# reg-board.net
KiCad netlist of a schematic drawn in EAGLE
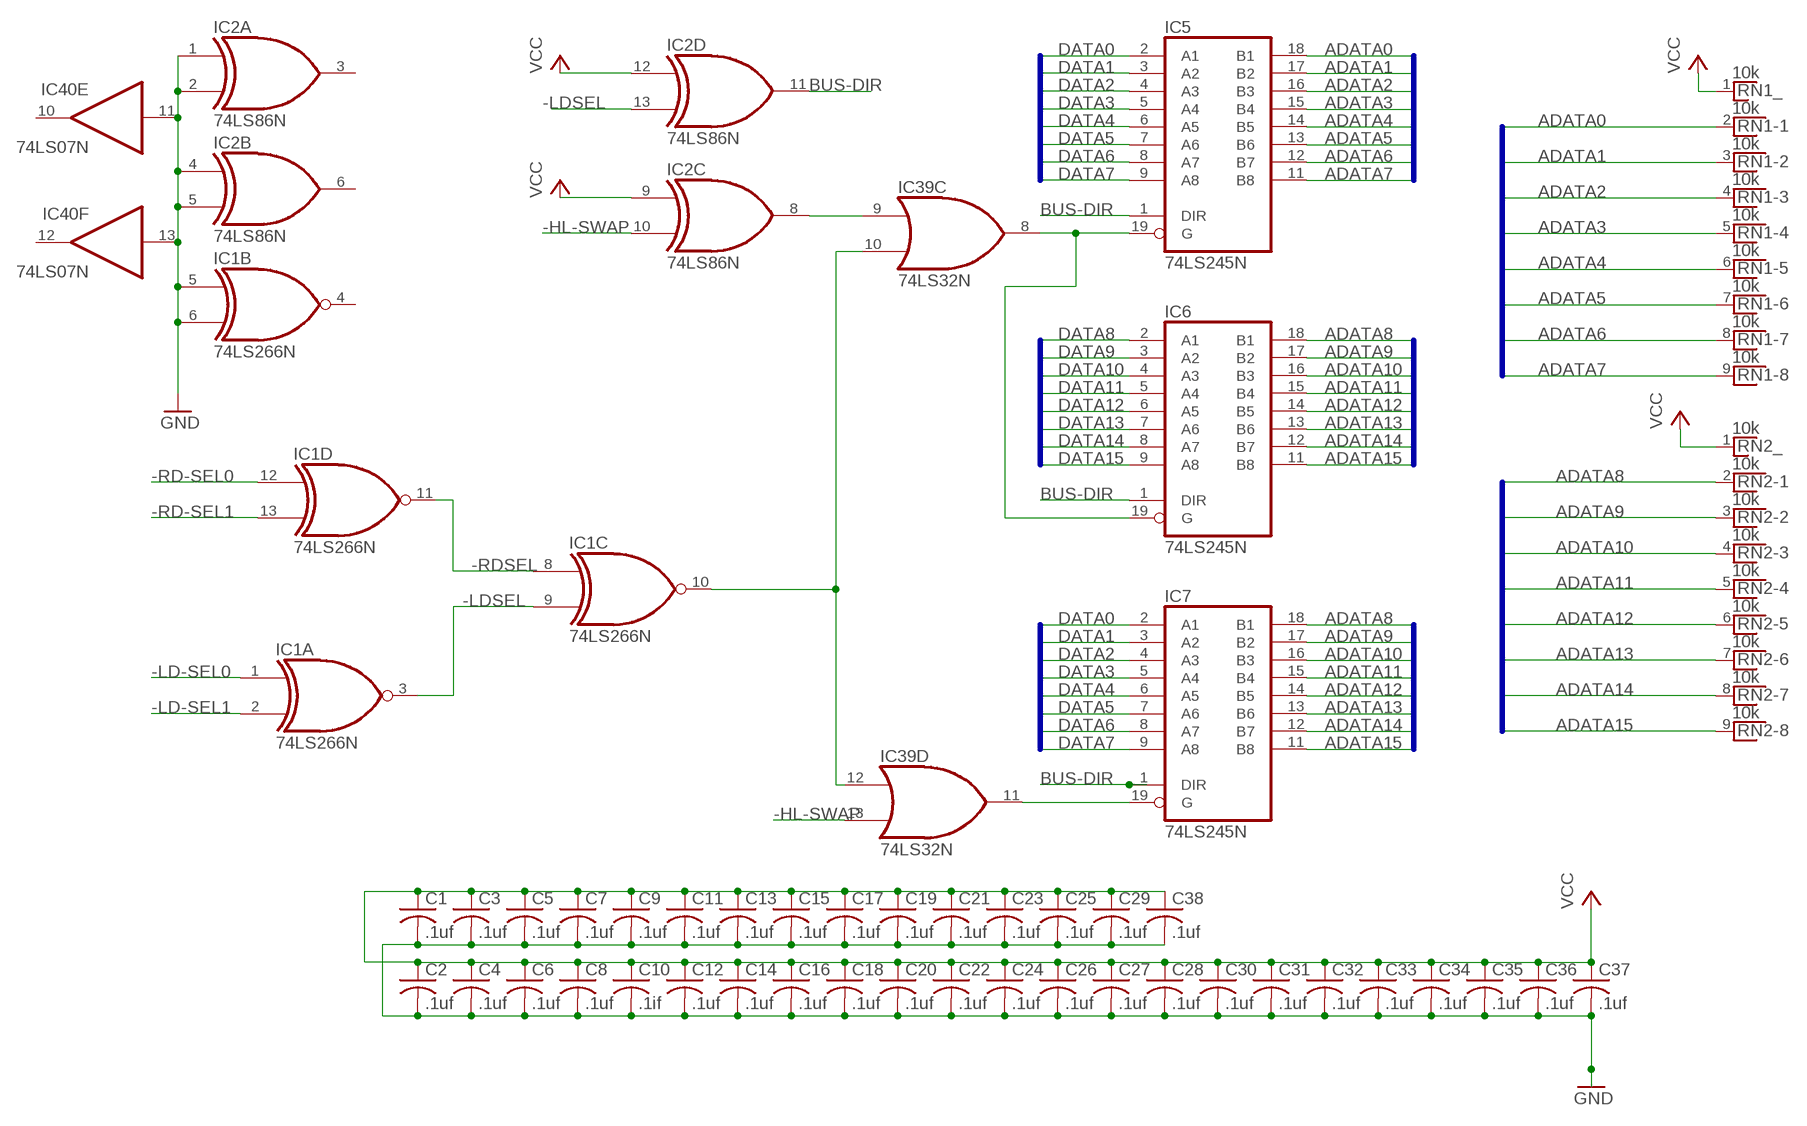
[diagram p0: schematic, sheet 1]
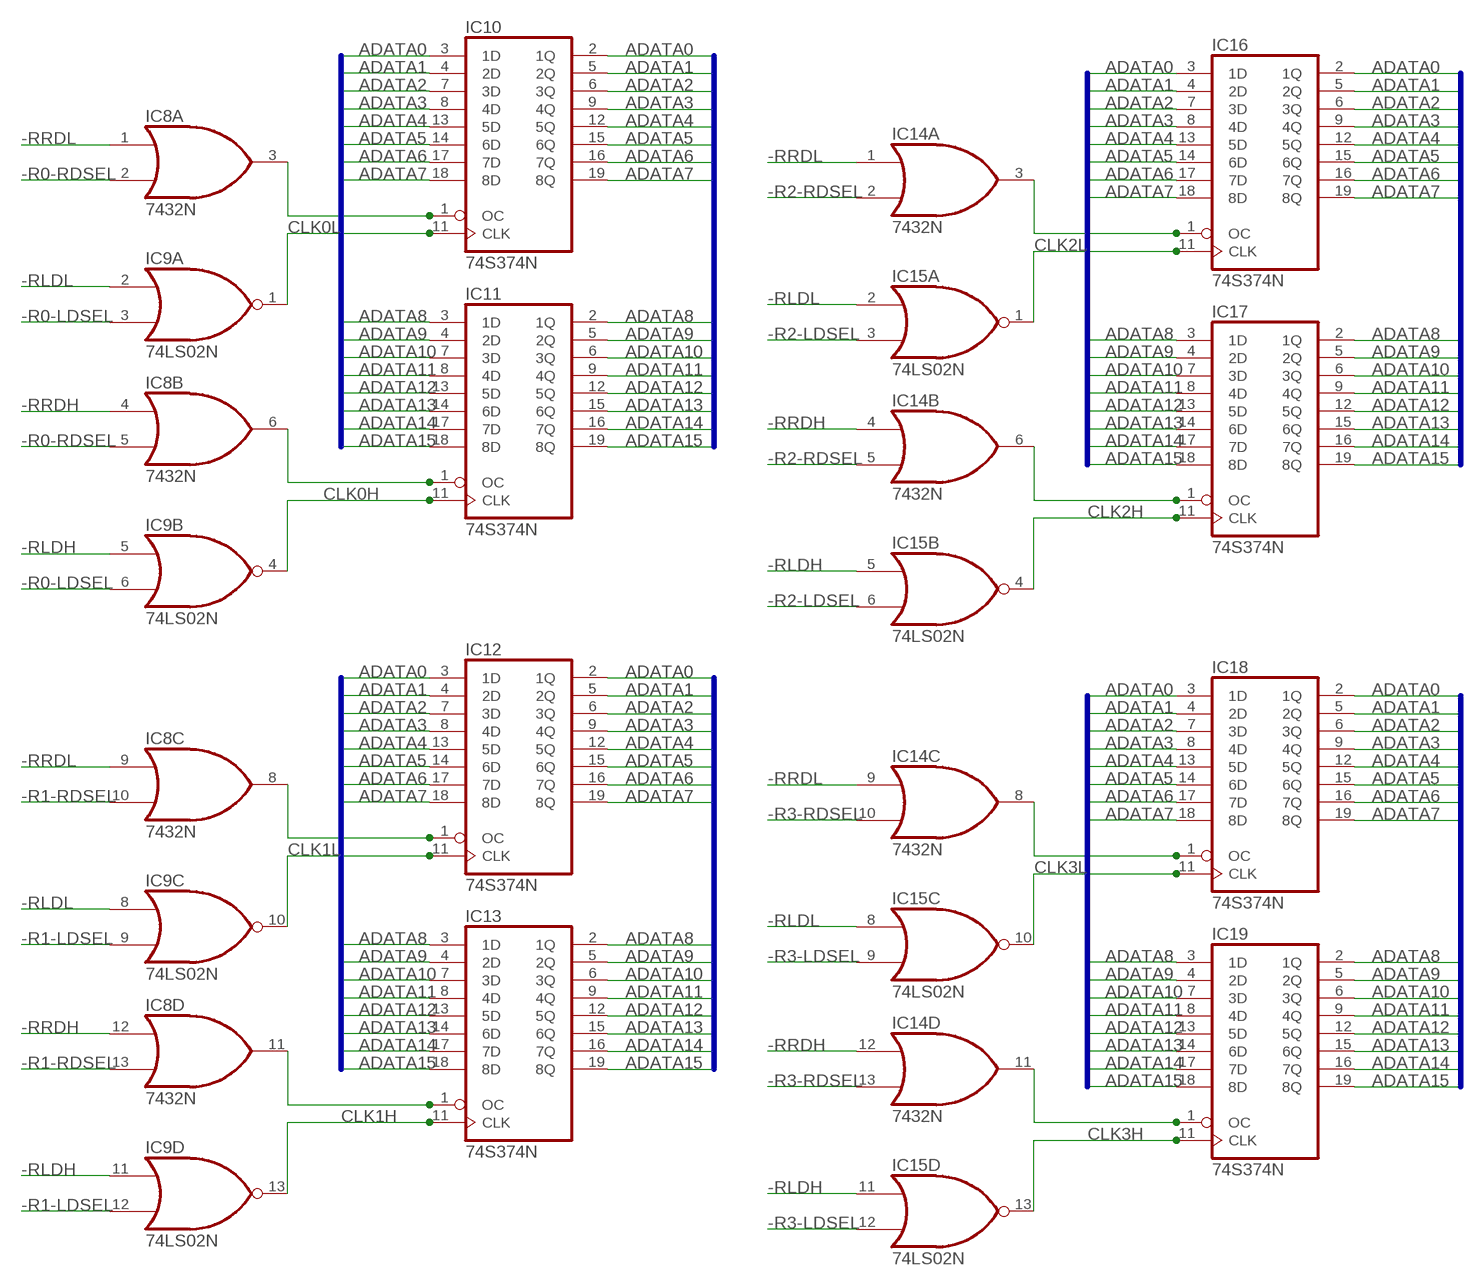
[diagram p1: schematic, sheet 2]
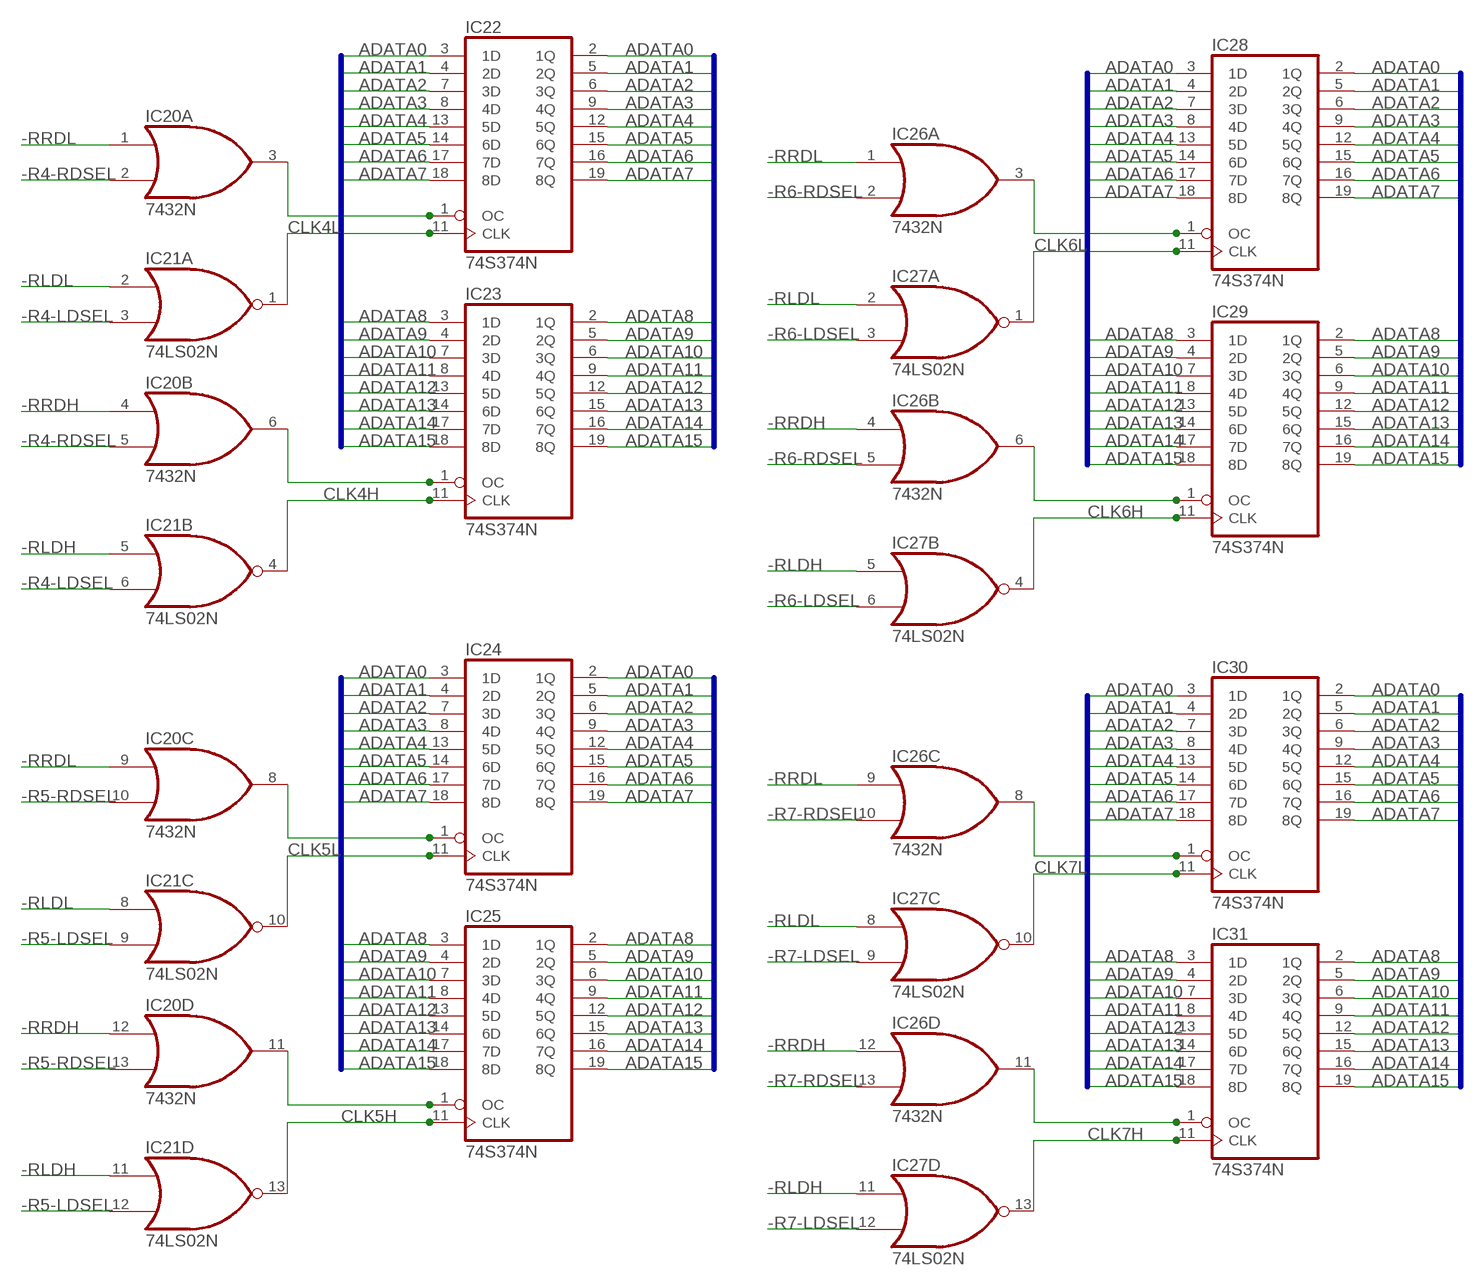
[diagram p2: schematic, sheet 3]
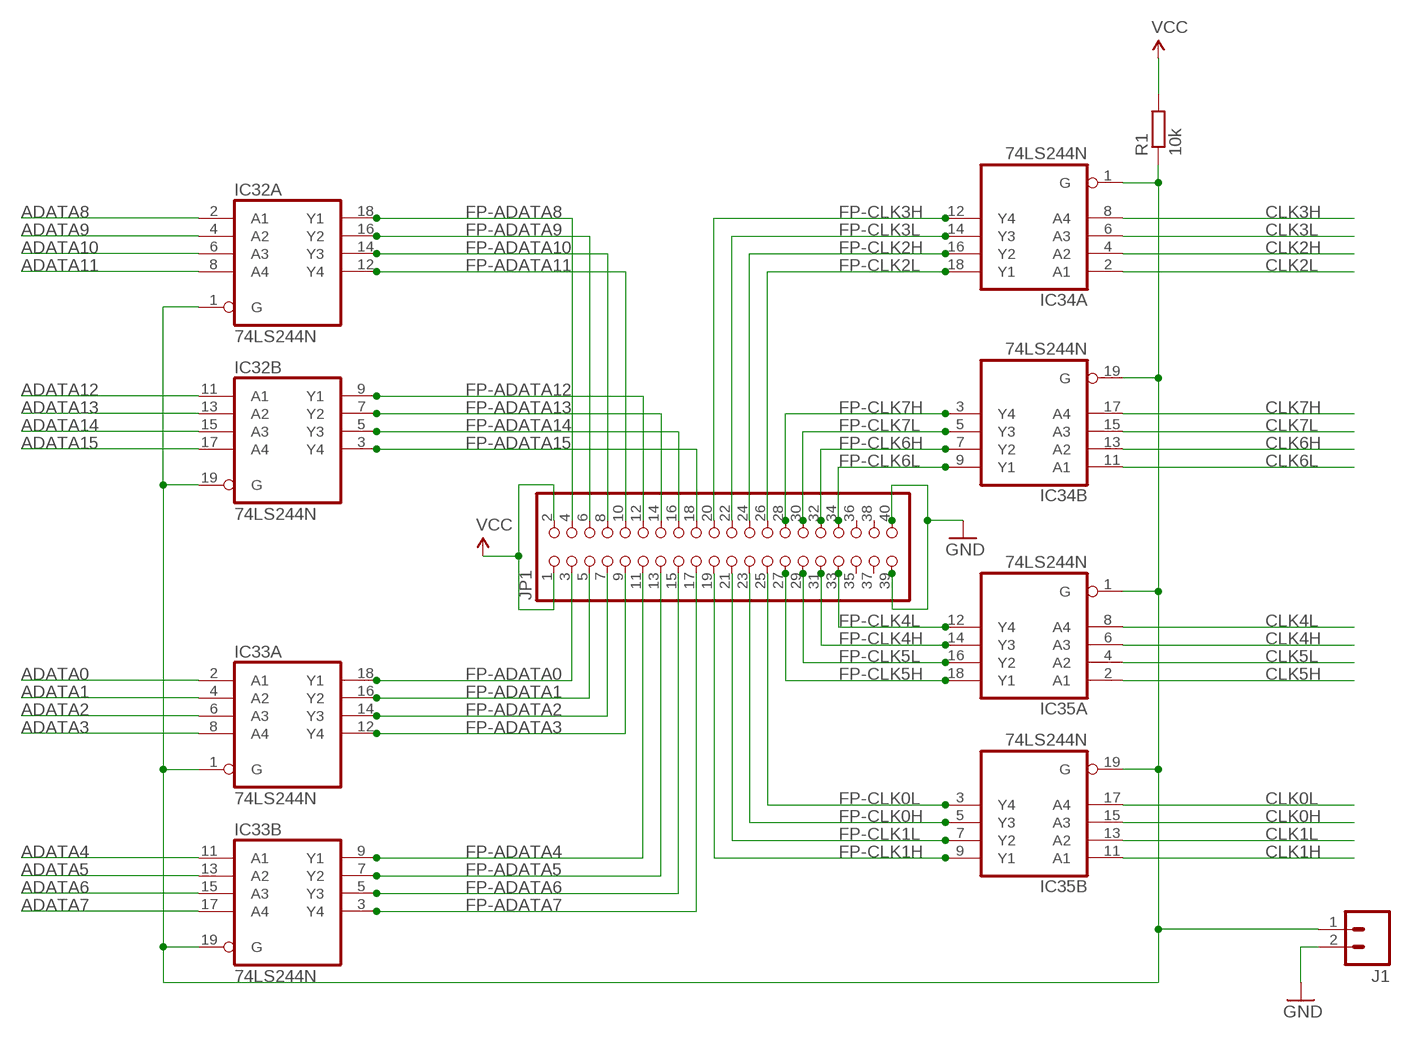
[diagram p3: schematic, sheet 4]
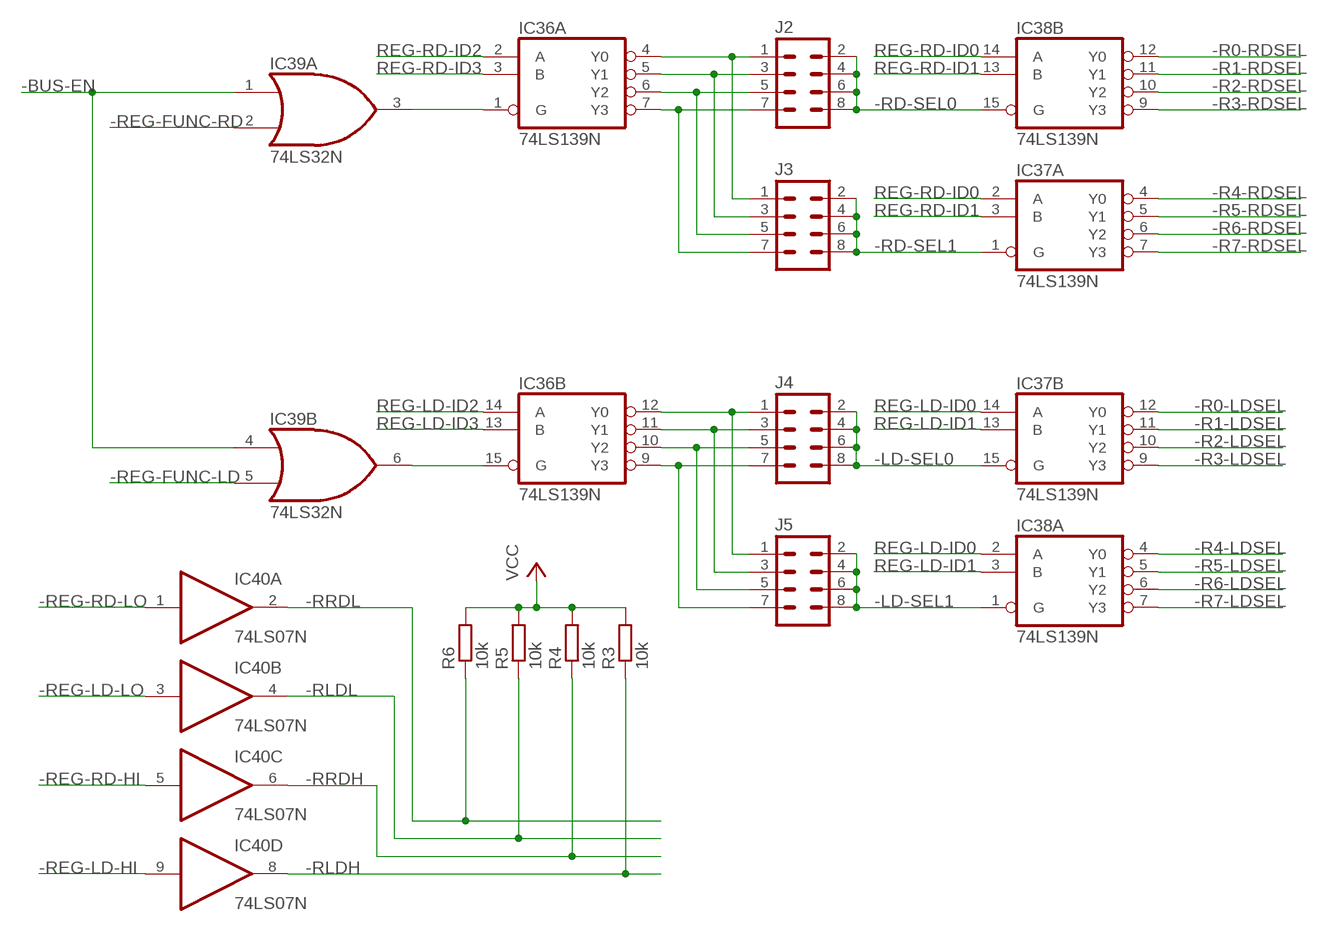
[diagram p4: schematic, sheet 5]
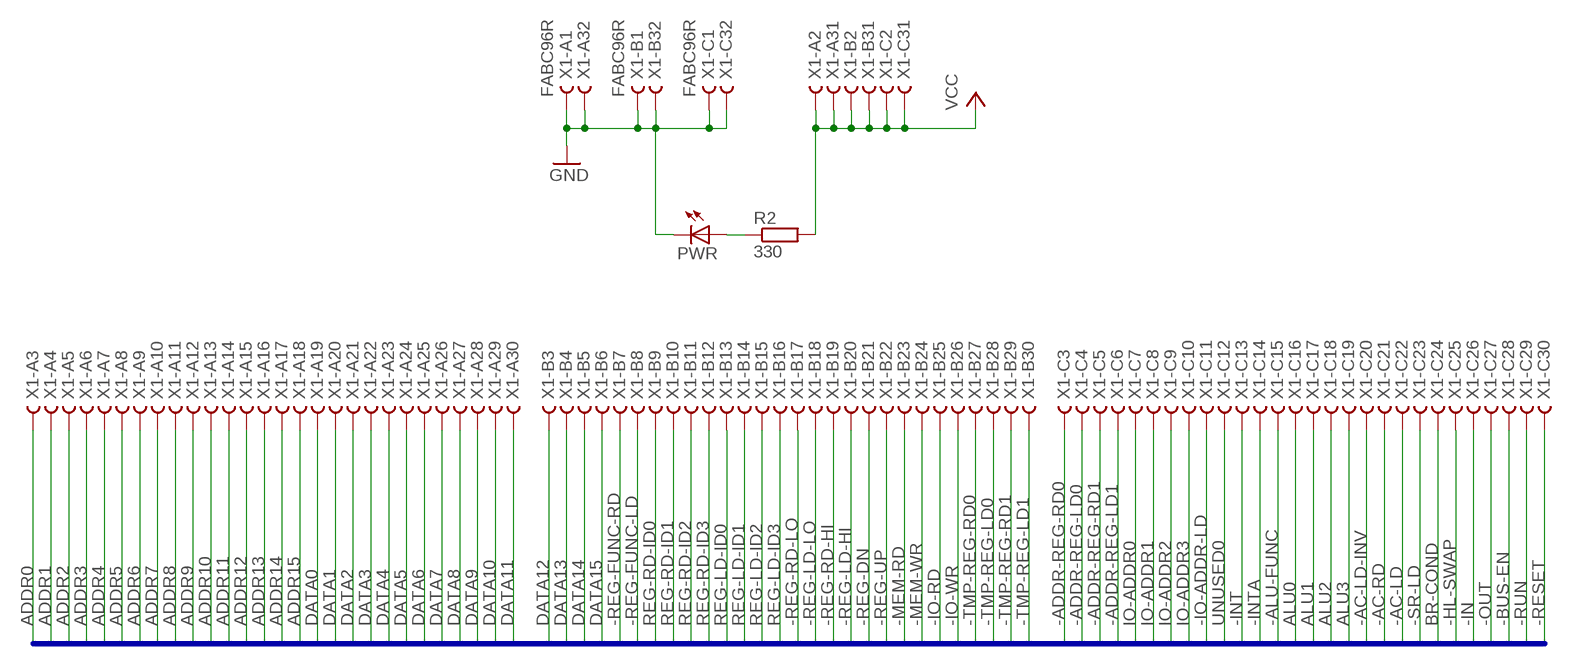
[diagram p5: schematic, sheet 6]

(export (version "E")
  (design (tool "Eeschema 10.0.6"))
  (components
    (comp (ref "IC8")
      (value "7432N")
      (footprint "eagle-import:DIL14")
      (libsource (lib "eagle-import") (part "7432N"))
    )
    (comp (ref "IC9")
      (value "74LS02N")
      (footprint "eagle-import:DIL14")
      (libsource (lib "eagle-import") (part "7402NLS"))
    )
    (comp (ref "IC10")
      (value "74S374N")
      (footprint "eagle-import:DIL20")
      (libsource (lib "eagle-import") (part "74374NS"))
    )
    (comp (ref "IC11")
      (value "74S374N")
      (footprint "eagle-import:DIL20")
      (libsource (lib "eagle-import") (part "74374NS"))
    )
    (comp (ref "IC12")
      (value "74S374N")
      (footprint "eagle-import:DIL20")
      (libsource (lib "eagle-import") (part "74374NS"))
    )
    (comp (ref "IC13")
      (value "74S374N")
      (footprint "eagle-import:DIL20")
      (libsource (lib "eagle-import") (part "74374NS"))
    )
    (comp (ref "IC14")
      (value "7432N")
      (footprint "eagle-import:DIL14")
      (libsource (lib "eagle-import") (part "7432N"))
    )
    (comp (ref "IC15")
      (value "74LS02N")
      (footprint "eagle-import:DIL14")
      (libsource (lib "eagle-import") (part "7402NLS"))
    )
    (comp (ref "IC16")
      (value "74S374N")
      (footprint "eagle-import:DIL20")
      (libsource (lib "eagle-import") (part "74374NS"))
    )
    (comp (ref "IC17")
      (value "74S374N")
      (footprint "eagle-import:DIL20")
      (libsource (lib "eagle-import") (part "74374NS"))
    )
    (comp (ref "IC18")
      (value "74S374N")
      (footprint "eagle-import:DIL20")
      (libsource (lib "eagle-import") (part "74374NS"))
    )
    (comp (ref "IC19")
      (value "74S374N")
      (footprint "eagle-import:DIL20")
      (libsource (lib "eagle-import") (part "74374NS"))
    )
    (comp (ref "C1")
      (value ".1uf")
      (footprint "eagle-import:C025-040X050")
      (libsource (lib "eagle-import") (part "C-US025-040X050"))
    )
    (comp (ref "C2")
      (value ".1uf")
      (footprint "eagle-import:C025-040X050")
      (libsource (lib "eagle-import") (part "C-US025-040X050"))
    )
    (comp (ref "C3")
      (value ".1uf")
      (footprint "eagle-import:C025-040X050")
      (libsource (lib "eagle-import") (part "C-US025-040X050"))
    )
    (comp (ref "C4")
      (value ".1uf")
      (footprint "eagle-import:C025-040X050")
      (libsource (lib "eagle-import") (part "C-US025-040X050"))
    )
    (comp (ref "C5")
      (value ".1uf")
      (footprint "eagle-import:C025-040X050")
      (libsource (lib "eagle-import") (part "C-US025-040X050"))
    )
    (comp (ref "C6")
      (value ".1uf")
      (footprint "eagle-import:C025-040X050")
      (libsource (lib "eagle-import") (part "C-US025-040X050"))
    )
    (comp (ref "C7")
      (value ".1uf")
      (footprint "eagle-import:C025-040X050")
      (libsource (lib "eagle-import") (part "C-US025-040X050"))
    )
    (comp (ref "C8")
      (value ".1uf")
      (footprint "eagle-import:C025-040X050")
      (libsource (lib "eagle-import") (part "C-US025-040X050"))
    )
    (comp (ref "C9")
      (value ".1uf")
      (footprint "eagle-import:C025-040X050")
      (libsource (lib "eagle-import") (part "C-US025-040X050"))
    )
    (comp (ref "C10")
      (value ".1if")
      (footprint "eagle-import:C025-040X050")
      (libsource (lib "eagle-import") (part "C-US025-040X050"))
    )
    (comp (ref "C11")
      (value ".1uf")
      (footprint "eagle-import:C025-040X050")
      (libsource (lib "eagle-import") (part "C-US025-040X050"))
    )
    (comp (ref "C12")
      (value ".1uf")
      (footprint "eagle-import:C025-040X050")
      (libsource (lib "eagle-import") (part "C-US025-040X050"))
    )
    (comp (ref "C13")
      (value ".1uf")
      (footprint "eagle-import:C025-040X050")
      (libsource (lib "eagle-import") (part "C-US025-040X050"))
    )
    (comp (ref "C14")
      (value ".1uf")
      (footprint "eagle-import:C025-040X050")
      (libsource (lib "eagle-import") (part "C-US025-040X050"))
    )
    (comp (ref "C15")
      (value ".1uf")
      (footprint "eagle-import:C025-040X050")
      (libsource (lib "eagle-import") (part "C-US025-040X050"))
    )
    (comp (ref "C16")
      (value ".1uf")
      (footprint "eagle-import:C025-040X050")
      (libsource (lib "eagle-import") (part "C-US025-040X050"))
    )
    (comp (ref "C17")
      (value ".1uf")
      (footprint "eagle-import:C025-040X050")
      (libsource (lib "eagle-import") (part "C-US025-040X050"))
    )
    (comp (ref "C18")
      (value ".1uf")
      (footprint "eagle-import:C025-040X050")
      (libsource (lib "eagle-import") (part "C-US025-040X050"))
    )
    (comp (ref "C19")
      (value ".1uf")
      (footprint "eagle-import:C025-040X050")
      (libsource (lib "eagle-import") (part "C-US025-040X050"))
    )
    (comp (ref "C20")
      (value ".1uf")
      (footprint "eagle-import:C025-040X050")
      (libsource (lib "eagle-import") (part "C-US025-040X050"))
    )
    (comp (ref "C21")
      (value ".1uf")
      (footprint "eagle-import:C025-040X050")
      (libsource (lib "eagle-import") (part "C-US025-040X050"))
    )
    (comp (ref "C22")
      (value ".1uf")
      (footprint "eagle-import:C025-040X050")
      (libsource (lib "eagle-import") (part "C-US025-040X050"))
    )
    (comp (ref "C23")
      (value ".1uf")
      (footprint "eagle-import:C025-040X050")
      (libsource (lib "eagle-import") (part "C-US025-040X050"))
    )
    (comp (ref "C24")
      (value ".1uf")
      (footprint "eagle-import:C025-040X050")
      (libsource (lib "eagle-import") (part "C-US025-040X050"))
    )
    (comp (ref "C25")
      (value ".1uf")
      (footprint "eagle-import:C025-040X050")
      (libsource (lib "eagle-import") (part "C-US025-040X050"))
    )
    (comp (ref "C26")
      (value ".1uf")
      (footprint "eagle-import:C025-040X050")
      (libsource (lib "eagle-import") (part "C-US025-040X050"))
    )
    (comp (ref "C27")
      (value ".1uf")
      (footprint "eagle-import:C025-040X050")
      (libsource (lib "eagle-import") (part "C-US025-040X050"))
    )
    (comp (ref "C28")
      (value ".1uf")
      (footprint "eagle-import:C025-040X050")
      (libsource (lib "eagle-import") (part "C-US025-040X050"))
    )
    (comp (ref "C29")
      (value ".1uf")
      (footprint "eagle-import:C025-040X050")
      (libsource (lib "eagle-import") (part "C-US025-040X050"))
    )
    (comp (ref "C30")
      (value ".1uf")
      (footprint "eagle-import:C025-040X050")
      (libsource (lib "eagle-import") (part "C-US025-040X050"))
    )
    (comp (ref "C31")
      (value ".1uf")
      (footprint "eagle-import:C025-040X050")
      (libsource (lib "eagle-import") (part "C-US025-040X050"))
    )
    (comp (ref "C32")
      (value ".1uf")
      (footprint "eagle-import:C025-040X050")
      (libsource (lib "eagle-import") (part "C-US025-040X050"))
    )
    (comp (ref "C33")
      (value ".1uf")
      (footprint "eagle-import:C025-040X050")
      (libsource (lib "eagle-import") (part "C-US025-040X050"))
    )
    (comp (ref "C34")
      (value ".1uf")
      (footprint "eagle-import:C025-040X050")
      (libsource (lib "eagle-import") (part "C-US025-040X050"))
    )
    (comp (ref "C35")
      (value ".1uf")
      (footprint "eagle-import:C025-040X050")
      (libsource (lib "eagle-import") (part "C-US025-040X050"))
    )
    (comp (ref "C36")
      (value ".1uf")
      (footprint "eagle-import:C025-040X050")
      (libsource (lib "eagle-import") (part "C-US025-040X050"))
    )
    (comp (ref "C37")
      (value ".1uf")
      (footprint "eagle-import:C025-040X050")
      (libsource (lib "eagle-import") (part "C-US025-040X050"))
    )
    (comp (ref "C38")
      (value ".1uf")
      (footprint "eagle-import:C025-040X050")
      (libsource (lib "eagle-import") (part "C-US025-040X050"))
    )
    (comp (ref "IC1")
      (value "74LS266N")
      (footprint "eagle-import:DIL14")
      (libsource (lib "eagle-import") (part "74266NLS"))
    )
    (comp (ref "IC2")
      (value "74LS86N")
      (footprint "eagle-import:DIL14")
      (libsource (lib "eagle-import") (part "7486NLS"))
    )
    (comp (ref "IC5")
      (value "74LS245N")
      (footprint "eagle-import:DIL20")
      (libsource (lib "eagle-import") (part "74245NLS"))
    )
    (comp (ref "IC6")
      (value "74LS245N")
      (footprint "eagle-import:DIL20")
      (libsource (lib "eagle-import") (part "74245NLS"))
    )
    (comp (ref "IC7")
      (value "74LS245N")
      (footprint "eagle-import:DIL20")
      (libsource (lib "eagle-import") (part "74245NLS"))
    )
    (comp (ref "IC39")
      (value "74LS32N")
      (footprint "eagle-import:DIL14")
      (libsource (lib "eagle-import") (part "74xx-us_88_7432NLS"))
    )
    (comp (ref "IC40")
      (value "74LS07N")
      (footprint "eagle-import:DIL14")
      (libsource (lib "eagle-import") (part "7407NLS"))
    )
    (comp (ref "RN1")
      (value "10k")
      (footprint "eagle-import:RN-9")
      (libsource (lib "eagle-import") (part "RNX8"))
    )
    (comp (ref "RN2")
      (value "10k")
      (footprint "eagle-import:RN-9")
      (libsource (lib "eagle-import") (part "RNX8"))
    )
    (comp (ref "IC36")
      (value "74LS139N")
      (footprint "eagle-import:DIL16")
      (libsource (lib "eagle-import") (part "74139NLS"))
    )
    (comp (ref "IC37")
      (value "74LS139N")
      (footprint "eagle-import:DIL16")
      (libsource (lib "eagle-import") (part "74139NLS"))
    )
    (comp (ref "IC38")
      (value "74LS139N")
      (footprint "eagle-import:DIL16")
      (libsource (lib "eagle-import") (part "74139NLS"))
    )
    (comp (ref "J2")
      (value "M04X2")
      (footprint "eagle-import:2X4")
      (libsource (lib "eagle-import") (part "M04X2"))
    )
    (comp (ref "J3")
      (value "M04X2")
      (footprint "eagle-import:2X4")
      (libsource (lib "eagle-import") (part "M04X2"))
    )
    (comp (ref "J4")
      (value "M04X2")
      (footprint "eagle-import:2X4")
      (libsource (lib "eagle-import") (part "M04X2"))
    )
    (comp (ref "J5")
      (value "M04X2")
      (footprint "eagle-import:2X4")
      (libsource (lib "eagle-import") (part "M04X2"))
    )
    (comp (ref "R3")
      (value "10k")
      (footprint "eagle-import:0207_10")
      (libsource (lib "eagle-import") (part "R0207/10"))
    )
    (comp (ref "R4")
      (value "10k")
      (footprint "eagle-import:0207_10")
      (libsource (lib "eagle-import") (part "R0207/10"))
    )
    (comp (ref "R5")
      (value "10k")
      (footprint "eagle-import:0207_10")
      (libsource (lib "eagle-import") (part "R0207/10"))
    )
    (comp (ref "R6")
      (value "10k")
      (footprint "eagle-import:0207_10")
      (libsource (lib "eagle-import") (part "R0207/10"))
    )
    (comp (ref "PWR")
      (value "LED5MM")
      (footprint "eagle-import:LED5MM")
      (libsource (lib "eagle-import") (part "LED5MM"))
    )
    (comp (ref "R2")
      (value "330")
      (footprint "eagle-import:0207_10")
      (libsource (lib "eagle-import") (part "R0207/10"))
    )
    (comp (ref "X1")
      (value "FABC96R")
      (footprint "eagle-import:FABC96R")
      (libsource (lib "eagle-import") (part "FABC96R"))
    )
    (comp (ref "IC20")
      (value "7432N")
      (footprint "eagle-import:DIL14")
      (libsource (lib "eagle-import") (part "7432N"))
    )
    (comp (ref "IC21")
      (value "74LS02N")
      (footprint "eagle-import:DIL14")
      (libsource (lib "eagle-import") (part "7402NLS"))
    )
    (comp (ref "IC22")
      (value "74S374N")
      (footprint "eagle-import:DIL20")
      (libsource (lib "eagle-import") (part "74374NS"))
    )
    (comp (ref "IC23")
      (value "74S374N")
      (footprint "eagle-import:DIL20")
      (libsource (lib "eagle-import") (part "74374NS"))
    )
    (comp (ref "IC24")
      (value "74S374N")
      (footprint "eagle-import:DIL20")
      (libsource (lib "eagle-import") (part "74374NS"))
    )
    (comp (ref "IC25")
      (value "74S374N")
      (footprint "eagle-import:DIL20")
      (libsource (lib "eagle-import") (part "74374NS"))
    )
    (comp (ref "IC26")
      (value "7432N")
      (footprint "eagle-import:DIL14")
      (libsource (lib "eagle-import") (part "7432N"))
    )
    (comp (ref "IC27")
      (value "74LS02N")
      (footprint "eagle-import:DIL14")
      (libsource (lib "eagle-import") (part "7402NLS"))
    )
    (comp (ref "IC28")
      (value "74S374N")
      (footprint "eagle-import:DIL20")
      (libsource (lib "eagle-import") (part "74374NS"))
    )
    (comp (ref "IC29")
      (value "74S374N")
      (footprint "eagle-import:DIL20")
      (libsource (lib "eagle-import") (part "74374NS"))
    )
    (comp (ref "IC30")
      (value "74S374N")
      (footprint "eagle-import:DIL20")
      (libsource (lib "eagle-import") (part "74374NS"))
    )
    (comp (ref "IC31")
      (value "74S374N")
      (footprint "eagle-import:DIL20")
      (libsource (lib "eagle-import") (part "74374NS"))
    )
    (comp (ref "IC32")
      (value "74LS244N")
      (footprint "eagle-import:DIL20")
      (libsource (lib "eagle-import") (part "74xx-us_74244NLS"))
    )
    (comp (ref "IC33")
      (value "74LS244N")
      (footprint "eagle-import:DIL20")
      (libsource (lib "eagle-import") (part "74xx-us_74244NLS"))
    )
    (comp (ref "IC34")
      (value "74LS244N")
      (footprint "eagle-import:DIL20")
      (libsource (lib "eagle-import") (part "74xx-us_74244NLS"))
    )
    (comp (ref "IC35")
      (value "74LS244N")
      (footprint "eagle-import:DIL20")
      (libsource (lib "eagle-import") (part "74xx-us_74244NLS"))
    )
    (comp (ref "J1")
      (value "M02PTH")
      (footprint "eagle-import:1X02")
      (libsource (lib "eagle-import") (part "M02PTH"))
    )
    (comp (ref "JP1")
      (value "PINHD-2X20")
      (footprint "eagle-import:2X20")
      (libsource (lib "eagle-import") (part "PINHD-2X20"))
    )
    (comp (ref "R1")
      (value "10k")
      (footprint "eagle-import:0207_10")
      (libsource (lib "eagle-import") (part "R0207/10"))
    )
  )
  (nets
    (net (code "1") (name "-AC-LD") (class "Default")
      (node (ref "X1") (pin "C22") (pinfunction "B_C22") (pintype "passive"))
    )
    (net (code "2") (name "-AC-LD-INV") (class "Default")
      (node (ref "X1") (pin "C20") (pinfunction "B_C20") (pintype "passive"))
    )
    (net (code "3") (name "-AC-RD") (class "Default")
      (node (ref "X1") (pin "C21") (pinfunction "B_C21") (pintype "passive"))
    )
    (net (code "4") (name "-ADDR-REG-LD0") (class "Default")
      (node (ref "X1") (pin "C4") (pinfunction "B_C4") (pintype "passive"))
    )
    (net (code "5") (name "-ADDR-REG-LD1") (class "Default")
      (node (ref "X1") (pin "C6") (pinfunction "B_C6") (pintype "passive"))
    )
    (net (code "6") (name "-ADDR-REG-RD0") (class "Default")
      (node (ref "X1") (pin "C3") (pinfunction "B_C3") (pintype "passive"))
    )
    (net (code "7") (name "-ADDR-REG-RD1") (class "Default")
      (node (ref "X1") (pin "C5") (pinfunction "B_C5") (pintype "passive"))
    )
    (net (code "8") (name "-ALU-FUNC") (class "Default")
      (node (ref "X1") (pin "C15") (pinfunction "B_C15") (pintype "passive"))
    )
    (net (code "9") (name "-BUS-EN") (class "Default")
      (node (ref "IC39") (pin "1") (pinfunction "I0_1") (pintype "input"))
      (node (ref "IC39") (pin "4") (pinfunction "I0_4") (pintype "input"))
      (node (ref "X1") (pin "C28") (pinfunction "B_C28") (pintype "passive"))
    )
    (net (code "10") (name "-HL-SWAP") (class "Default")
      (node (ref "IC2") (pin "10") (pinfunction "I1_10") (pintype "input"))
      (node (ref "IC39") (pin "13") (pinfunction "I1_13") (pintype "input"))
      (node (ref "X1") (pin "C25") (pinfunction "B_C25") (pintype "passive"))
    )
    (net (code "11") (name "-IN") (class "Default")
      (node (ref "X1") (pin "C26") (pinfunction "B_C26") (pintype "passive"))
    )
    (net (code "12") (name "-INT") (class "Default")
      (node (ref "X1") (pin "C13") (pinfunction "B_C13") (pintype "passive"))
    )
    (net (code "13") (name "-INTA") (class "Default")
      (node (ref "X1") (pin "C14") (pinfunction "B_C14") (pintype "passive"))
    )
    (net (code "14") (name "-IO-ADDR-LD") (class "Default")
      (node (ref "X1") (pin "C11") (pinfunction "B_C11") (pintype "passive"))
    )
    (net (code "15") (name "-IO-RD") (class "Default")
      (node (ref "X1") (pin "B25") (pinfunction "B_B25") (pintype "passive"))
    )
    (net (code "16") (name "-IO-WR") (class "Default")
      (node (ref "X1") (pin "B26") (pinfunction "B_B26") (pintype "passive"))
    )
    (net (code "17") (name "-LD-SEL0") (class "Default")
      (node (ref "IC1") (pin "1") (pinfunction "I0_1") (pintype "input"))
      (node (ref "IC37") (pin "15") (pinfunction "G_15") (pintype "input"))
      (node (ref "J4") (pin "2") (pinfunction "2_2") (pintype "passive"))
      (node (ref "J4") (pin "4") (pinfunction "4_4") (pintype "passive"))
      (node (ref "J4") (pin "6") (pinfunction "6_6") (pintype "passive"))
      (node (ref "J4") (pin "8") (pinfunction "8_8") (pintype "passive"))
    )
    (net (code "18") (name "-LD-SEL1") (class "Default")
      (node (ref "IC1") (pin "2") (pinfunction "I1_2") (pintype "input"))
      (node (ref "IC38") (pin "1") (pinfunction "G_1") (pintype "input"))
      (node (ref "J5") (pin "2") (pinfunction "2_2") (pintype "passive"))
      (node (ref "J5") (pin "4") (pinfunction "4_4") (pintype "passive"))
      (node (ref "J5") (pin "6") (pinfunction "6_6") (pintype "passive"))
      (node (ref "J5") (pin "8") (pinfunction "8_8") (pintype "passive"))
    )
    (net (code "19") (name "-LDSEL") (class "Default")
      (node (ref "IC1") (pin "3") (pinfunction "O_3") (pintype "open_collector"))
      (node (ref "IC1") (pin "9") (pinfunction "I1_9") (pintype "input"))
      (node (ref "IC2") (pin "13") (pinfunction "I1_13") (pintype "input"))
    )
    (net (code "20") (name "-MEM-RD") (class "Default")
      (node (ref "X1") (pin "B23") (pinfunction "B_B23") (pintype "passive"))
    )
    (net (code "21") (name "-MEM-WR") (class "Default")
      (node (ref "X1") (pin "B24") (pinfunction "B_B24") (pintype "passive"))
    )
    (net (code "22") (name "-OUT") (class "Default")
      (node (ref "X1") (pin "C27") (pinfunction "B_C27") (pintype "passive"))
    )
    (net (code "23") (name "-R0-LDSEL") (class "Default")
      (node (ref "IC37") (pin "12") (pinfunction "Y0_12") (pintype "output"))
      (node (ref "IC9") (pin "3") (pinfunction "I1_3") (pintype "input"))
      (node (ref "IC9") (pin "6") (pinfunction "I1_6") (pintype "input"))
    )
    (net (code "24") (name "-R0-RDSEL") (class "Default")
      (node (ref "IC38") (pin "12") (pinfunction "Y0_12") (pintype "output"))
      (node (ref "IC8") (pin "2") (pinfunction "I1_2") (pintype "input"))
      (node (ref "IC8") (pin "5") (pinfunction "I1_5") (pintype "input"))
    )
    (net (code "25") (name "-R1-LDSEL") (class "Default")
      (node (ref "IC37") (pin "11") (pinfunction "Y1_11") (pintype "output"))
      (node (ref "IC9") (pin "12") (pinfunction "I1_12") (pintype "input"))
      (node (ref "IC9") (pin "9") (pinfunction "I1_9") (pintype "input"))
    )
    (net (code "26") (name "-R1-RDSEL") (class "Default")
      (node (ref "IC38") (pin "11") (pinfunction "Y1_11") (pintype "output"))
      (node (ref "IC8") (pin "10") (pinfunction "I1_10") (pintype "input"))
      (node (ref "IC8") (pin "13") (pinfunction "I1_13") (pintype "input"))
    )
    (net (code "27") (name "-R2-LDSEL") (class "Default")
      (node (ref "IC15") (pin "3") (pinfunction "I1_3") (pintype "input"))
      (node (ref "IC15") (pin "6") (pinfunction "I1_6") (pintype "input"))
      (node (ref "IC37") (pin "10") (pinfunction "Y2_10") (pintype "output"))
    )
    (net (code "28") (name "-R2-RDSEL") (class "Default")
      (node (ref "IC14") (pin "2") (pinfunction "I1_2") (pintype "input"))
      (node (ref "IC14") (pin "5") (pinfunction "I1_5") (pintype "input"))
      (node (ref "IC38") (pin "10") (pinfunction "Y2_10") (pintype "output"))
    )
    (net (code "29") (name "-R3-LDSEL") (class "Default")
      (node (ref "IC15") (pin "12") (pinfunction "I1_12") (pintype "input"))
      (node (ref "IC15") (pin "9") (pinfunction "I1_9") (pintype "input"))
      (node (ref "IC37") (pin "9") (pinfunction "Y3_9") (pintype "output"))
    )
    (net (code "30") (name "-R3-RDSEL") (class "Default")
      (node (ref "IC14") (pin "10") (pinfunction "I1_10") (pintype "input"))
      (node (ref "IC14") (pin "13") (pinfunction "I1_13") (pintype "input"))
      (node (ref "IC38") (pin "9") (pinfunction "Y3_9") (pintype "output"))
    )
    (net (code "31") (name "-R4-LDSEL") (class "Default")
      (node (ref "IC21") (pin "3") (pinfunction "I1_3") (pintype "input"))
      (node (ref "IC21") (pin "6") (pinfunction "I1_6") (pintype "input"))
      (node (ref "IC38") (pin "4") (pinfunction "Y0_4") (pintype "output"))
    )
    (net (code "32") (name "-R4-RDSEL") (class "Default")
      (node (ref "IC20") (pin "2") (pinfunction "I1_2") (pintype "input"))
      (node (ref "IC20") (pin "5") (pinfunction "I1_5") (pintype "input"))
      (node (ref "IC37") (pin "4") (pinfunction "Y0_4") (pintype "output"))
    )
    (net (code "33") (name "-R5-LDSEL") (class "Default")
      (node (ref "IC21") (pin "12") (pinfunction "I1_12") (pintype "input"))
      (node (ref "IC21") (pin "9") (pinfunction "I1_9") (pintype "input"))
      (node (ref "IC38") (pin "5") (pinfunction "Y1_5") (pintype "output"))
    )
    (net (code "34") (name "-R5-RDSEL") (class "Default")
      (node (ref "IC20") (pin "10") (pinfunction "I1_10") (pintype "input"))
      (node (ref "IC20") (pin "13") (pinfunction "I1_13") (pintype "input"))
      (node (ref "IC37") (pin "5") (pinfunction "Y1_5") (pintype "output"))
    )
    (net (code "35") (name "-R6-LDSEL") (class "Default")
      (node (ref "IC27") (pin "3") (pinfunction "I1_3") (pintype "input"))
      (node (ref "IC27") (pin "6") (pinfunction "I1_6") (pintype "input"))
      (node (ref "IC38") (pin "6") (pinfunction "Y2_6") (pintype "output"))
    )
    (net (code "36") (name "-R6-RDSEL") (class "Default")
      (node (ref "IC26") (pin "2") (pinfunction "I1_2") (pintype "input"))
      (node (ref "IC26") (pin "5") (pinfunction "I1_5") (pintype "input"))
      (node (ref "IC37") (pin "6") (pinfunction "Y2_6") (pintype "output"))
    )
    (net (code "37") (name "-R7-LDSEL") (class "Default")
      (node (ref "IC27") (pin "12") (pinfunction "I1_12") (pintype "input"))
      (node (ref "IC27") (pin "9") (pinfunction "I1_9") (pintype "input"))
      (node (ref "IC38") (pin "7") (pinfunction "Y3_7") (pintype "output"))
    )
    (net (code "38") (name "-R7-RDSEL") (class "Default")
      (node (ref "IC26") (pin "10") (pinfunction "I1_10") (pintype "input"))
      (node (ref "IC26") (pin "13") (pinfunction "I1_13") (pintype "input"))
      (node (ref "IC37") (pin "7") (pinfunction "Y3_7") (pintype "output"))
    )
    (net (code "39") (name "-RD-SEL0") (class "Default")
      (node (ref "IC1") (pin "12") (pinfunction "I0_12") (pintype "input"))
      (node (ref "IC38") (pin "15") (pinfunction "G_15") (pintype "input"))
      (node (ref "J2") (pin "2") (pinfunction "2_2") (pintype "passive"))
      (node (ref "J2") (pin "4") (pinfunction "4_4") (pintype "passive"))
      (node (ref "J2") (pin "6") (pinfunction "6_6") (pintype "passive"))
      (node (ref "J2") (pin "8") (pinfunction "8_8") (pintype "passive"))
    )
    (net (code "40") (name "-RD-SEL1") (class "Default")
      (node (ref "IC1") (pin "13") (pinfunction "I1_13") (pintype "input"))
      (node (ref "IC37") (pin "1") (pinfunction "G_1") (pintype "input"))
      (node (ref "J3") (pin "2") (pinfunction "2_2") (pintype "passive"))
      (node (ref "J3") (pin "4") (pinfunction "4_4") (pintype "passive"))
      (node (ref "J3") (pin "6") (pinfunction "6_6") (pintype "passive"))
      (node (ref "J3") (pin "8") (pinfunction "8_8") (pintype "passive"))
    )
    (net (code "41") (name "-RDSEL") (class "Default")
      (node (ref "IC1") (pin "11") (pinfunction "O_11") (pintype "open_collector"))
      (node (ref "IC1") (pin "8") (pinfunction "I0_8") (pintype "input"))
    )
    (net (code "42") (name "-REG-DN") (class "Default")
      (node (ref "X1") (pin "B21") (pinfunction "B_B21") (pintype "passive"))
    )
    (net (code "43") (name "-REG-FUNC-LD") (class "Default")
      (node (ref "IC39") (pin "5") (pinfunction "I1_5") (pintype "input"))
      (node (ref "X1") (pin "B8") (pinfunction "B_B8") (pintype "passive"))
    )
    (net (code "44") (name "-REG-FUNC-RD") (class "Default")
      (node (ref "IC39") (pin "2") (pinfunction "I1_2") (pintype "input"))
      (node (ref "X1") (pin "B7") (pinfunction "B_B7") (pintype "passive"))
    )
    (net (code "45") (name "-REG-LD-HI") (class "Default")
      (node (ref "IC40") (pin "9") (pinfunction "I_9") (pintype "input"))
      (node (ref "X1") (pin "B20") (pinfunction "B_B20") (pintype "passive"))
    )
    (net (code "46") (name "-REG-LD-LO") (class "Default")
      (node (ref "IC40") (pin "3") (pinfunction "I_3") (pintype "input"))
      (node (ref "X1") (pin "B18") (pinfunction "B_B18") (pintype "passive"))
    )
    (net (code "47") (name "-REG-RD-HI") (class "Default")
      (node (ref "IC40") (pin "5") (pinfunction "I_5") (pintype "input"))
      (node (ref "X1") (pin "B19") (pinfunction "B_B19") (pintype "passive"))
    )
    (net (code "48") (name "-REG-RD-LO") (class "Default")
      (node (ref "IC40") (pin "1") (pinfunction "I_1") (pintype "input"))
      (node (ref "X1") (pin "B17") (pinfunction "B_B17") (pintype "passive"))
    )
    (net (code "49") (name "-REG-UP") (class "Default")
      (node (ref "X1") (pin "B22") (pinfunction "B_B22") (pintype "passive"))
    )
    (net (code "50") (name "-RESET") (class "Default")
      (node (ref "X1") (pin "C30") (pinfunction "B_C30") (pintype "passive"))
    )
    (net (code "51") (name "-RLDH") (class "Default")
      (node (ref "IC15") (pin "11") (pinfunction "I0_11") (pintype "input"))
      (node (ref "IC15") (pin "5") (pinfunction "I0_5") (pintype "input"))
      (node (ref "IC21") (pin "11") (pinfunction "I0_11") (pintype "input"))
      (node (ref "IC21") (pin "5") (pinfunction "I0_5") (pintype "input"))
      (node (ref "IC27") (pin "11") (pinfunction "I0_11") (pintype "input"))
      (node (ref "IC27") (pin "5") (pinfunction "I0_5") (pintype "input"))
      (node (ref "IC40") (pin "8") (pinfunction "O_8") (pintype "open_collector"))
      (node (ref "IC9") (pin "11") (pinfunction "I0_11") (pintype "input"))
      (node (ref "IC9") (pin "5") (pinfunction "I0_5") (pintype "input"))
      (node (ref "R3") (pin "1") (pinfunction "1_1") (pintype "passive"))
    )
    (net (code "52") (name "-RLDL") (class "Default")
      (node (ref "IC15") (pin "2") (pinfunction "I0_2") (pintype "input"))
      (node (ref "IC15") (pin "8") (pinfunction "I0_8") (pintype "input"))
      (node (ref "IC21") (pin "2") (pinfunction "I0_2") (pintype "input"))
      (node (ref "IC21") (pin "8") (pinfunction "I0_8") (pintype "input"))
      (node (ref "IC27") (pin "2") (pinfunction "I0_2") (pintype "input"))
      (node (ref "IC27") (pin "8") (pinfunction "I0_8") (pintype "input"))
      (node (ref "IC40") (pin "4") (pinfunction "O_4") (pintype "open_collector"))
      (node (ref "IC9") (pin "2") (pinfunction "I0_2") (pintype "input"))
      (node (ref "IC9") (pin "8") (pinfunction "I0_8") (pintype "input"))
      (node (ref "R5") (pin "1") (pinfunction "1_1") (pintype "passive"))
    )
    (net (code "53") (name "-RRDH") (class "Default")
      (node (ref "IC14") (pin "12") (pinfunction "I0_12") (pintype "input"))
      (node (ref "IC14") (pin "4") (pinfunction "I0_4") (pintype "input"))
      (node (ref "IC20") (pin "12") (pinfunction "I0_12") (pintype "input"))
      (node (ref "IC20") (pin "4") (pinfunction "I0_4") (pintype "input"))
      (node (ref "IC26") (pin "12") (pinfunction "I0_12") (pintype "input"))
      (node (ref "IC26") (pin "4") (pinfunction "I0_4") (pintype "input"))
      (node (ref "IC40") (pin "6") (pinfunction "O_6") (pintype "open_collector"))
      (node (ref "IC8") (pin "12") (pinfunction "I0_12") (pintype "input"))
      (node (ref "IC8") (pin "4") (pinfunction "I0_4") (pintype "input"))
      (node (ref "R4") (pin "1") (pinfunction "1_1") (pintype "passive"))
    )
    (net (code "54") (name "-RRDL") (class "Default")
      (node (ref "IC14") (pin "1") (pinfunction "I0_1") (pintype "input"))
      (node (ref "IC14") (pin "9") (pinfunction "I0_9") (pintype "input"))
      (node (ref "IC20") (pin "1") (pinfunction "I0_1") (pintype "input"))
      (node (ref "IC20") (pin "9") (pinfunction "I0_9") (pintype "input"))
      (node (ref "IC26") (pin "1") (pinfunction "I0_1") (pintype "input"))
      (node (ref "IC26") (pin "9") (pinfunction "I0_9") (pintype "input"))
      (node (ref "IC40") (pin "2") (pinfunction "O_2") (pintype "open_collector"))
      (node (ref "IC8") (pin "1") (pinfunction "I0_1") (pintype "input"))
      (node (ref "IC8") (pin "9") (pinfunction "I0_9") (pintype "input"))
      (node (ref "R6") (pin "1") (pinfunction "1_1") (pintype "passive"))
    )
    (net (code "55") (name "-RUN") (class "Default")
      (node (ref "X1") (pin "C29") (pinfunction "B_C29") (pintype "passive"))
    )
    (net (code "56") (name "-SR-LD") (class "Default")
      (node (ref "X1") (pin "C23") (pinfunction "B_C23") (pintype "passive"))
    )
    (net (code "57") (name "-TMP-REG-LD0") (class "Default")
      (node (ref "X1") (pin "B28") (pinfunction "B_B28") (pintype "passive"))
    )
    (net (code "58") (name "-TMP-REG-LD1") (class "Default")
      (node (ref "X1") (pin "B30") (pinfunction "B_B30") (pintype "passive"))
    )
    (net (code "59") (name "-TMP-REG-RD0") (class "Default")
      (node (ref "X1") (pin "B27") (pinfunction "B_B27") (pintype "passive"))
    )
    (net (code "60") (name "-TMP-REG-RD1") (class "Default")
      (node (ref "X1") (pin "B29") (pinfunction "B_B29") (pintype "passive"))
    )
    (net (code "61") (name "ADATA0") (class "Default")
      (node (ref "IC10") (pin "2") (pinfunction "1Q_2") (pintype "tri_state"))
      (node (ref "IC10") (pin "3") (pinfunction "1D_3") (pintype "input"))
      (node (ref "IC12") (pin "2") (pinfunction "1Q_2") (pintype "tri_state"))
      (node (ref "IC12") (pin "3") (pinfunction "1D_3") (pintype "input"))
      (node (ref "IC16") (pin "2") (pinfunction "1Q_2") (pintype "tri_state"))
      (node (ref "IC16") (pin "3") (pinfunction "1D_3") (pintype "input"))
      (node (ref "IC18") (pin "2") (pinfunction "1Q_2") (pintype "tri_state"))
      (node (ref "IC18") (pin "3") (pinfunction "1D_3") (pintype "input"))
      (node (ref "IC22") (pin "2") (pinfunction "1Q_2") (pintype "tri_state"))
      (node (ref "IC22") (pin "3") (pinfunction "1D_3") (pintype "input"))
      (node (ref "IC24") (pin "2") (pinfunction "1Q_2") (pintype "tri_state"))
      (node (ref "IC24") (pin "3") (pinfunction "1D_3") (pintype "input"))
      (node (ref "IC28") (pin "2") (pinfunction "1Q_2") (pintype "tri_state"))
      (node (ref "IC28") (pin "3") (pinfunction "1D_3") (pintype "input"))
      (node (ref "IC30") (pin "2") (pinfunction "1Q_2") (pintype "tri_state"))
      (node (ref "IC30") (pin "3") (pinfunction "1D_3") (pintype "input"))
      (node (ref "IC33") (pin "2") (pinfunction "A1_2") (pintype "input"))
      (node (ref "IC5") (pin "18") (pinfunction "B1_18") (pintype "bidirectional"))
      (node (ref "RN1") (pin "2") (pinfunction "1_2") (pintype "passive"))
    )
    (net (code "62") (name "ADATA1") (class "Default")
      (node (ref "IC10") (pin "4") (pinfunction "2D_4") (pintype "input"))
      (node (ref "IC10") (pin "5") (pinfunction "2Q_5") (pintype "tri_state"))
      (node (ref "IC12") (pin "4") (pinfunction "2D_4") (pintype "input"))
      (node (ref "IC12") (pin "5") (pinfunction "2Q_5") (pintype "tri_state"))
      (node (ref "IC16") (pin "4") (pinfunction "2D_4") (pintype "input"))
      (node (ref "IC16") (pin "5") (pinfunction "2Q_5") (pintype "tri_state"))
      (node (ref "IC18") (pin "4") (pinfunction "2D_4") (pintype "input"))
      (node (ref "IC18") (pin "5") (pinfunction "2Q_5") (pintype "tri_state"))
      (node (ref "IC22") (pin "4") (pinfunction "2D_4") (pintype "input"))
      (node (ref "IC22") (pin "5") (pinfunction "2Q_5") (pintype "tri_state"))
      (node (ref "IC24") (pin "4") (pinfunction "2D_4") (pintype "input"))
      (node (ref "IC24") (pin "5") (pinfunction "2Q_5") (pintype "tri_state"))
      (node (ref "IC28") (pin "4") (pinfunction "2D_4") (pintype "input"))
      (node (ref "IC28") (pin "5") (pinfunction "2Q_5") (pintype "tri_state"))
      (node (ref "IC30") (pin "4") (pinfunction "2D_4") (pintype "input"))
      (node (ref "IC30") (pin "5") (pinfunction "2Q_5") (pintype "tri_state"))
      (node (ref "IC33") (pin "4") (pinfunction "A2_4") (pintype "input"))
      (node (ref "IC5") (pin "17") (pinfunction "B2_17") (pintype "bidirectional"))
      (node (ref "RN1") (pin "3") (pinfunction "1_3") (pintype "passive"))
    )
    (net (code "63") (name "ADATA2") (class "Default")
      (node (ref "IC10") (pin "6") (pinfunction "3Q_6") (pintype "tri_state"))
      (node (ref "IC10") (pin "7") (pinfunction "3D_7") (pintype "input"))
      (node (ref "IC12") (pin "6") (pinfunction "3Q_6") (pintype "tri_state"))
      (node (ref "IC12") (pin "7") (pinfunction "3D_7") (pintype "input"))
      (node (ref "IC16") (pin "6") (pinfunction "3Q_6") (pintype "tri_state"))
      (node (ref "IC16") (pin "7") (pinfunction "3D_7") (pintype "input"))
      (node (ref "IC18") (pin "6") (pinfunction "3Q_6") (pintype "tri_state"))
      (node (ref "IC18") (pin "7") (pinfunction "3D_7") (pintype "input"))
      (node (ref "IC22") (pin "6") (pinfunction "3Q_6") (pintype "tri_state"))
      (node (ref "IC22") (pin "7") (pinfunction "3D_7") (pintype "input"))
      (node (ref "IC24") (pin "6") (pinfunction "3Q_6") (pintype "tri_state"))
      (node (ref "IC24") (pin "7") (pinfunction "3D_7") (pintype "input"))
      (node (ref "IC28") (pin "6") (pinfunction "3Q_6") (pintype "tri_state"))
      (node (ref "IC28") (pin "7") (pinfunction "3D_7") (pintype "input"))
      (node (ref "IC30") (pin "6") (pinfunction "3Q_6") (pintype "tri_state"))
      (node (ref "IC30") (pin "7") (pinfunction "3D_7") (pintype "input"))
      (node (ref "IC33") (pin "6") (pinfunction "A3_6") (pintype "input"))
      (node (ref "IC5") (pin "16") (pinfunction "B3_16") (pintype "bidirectional"))
      (node (ref "RN1") (pin "4") (pinfunction "1_4") (pintype "passive"))
    )
    (net (code "64") (name "ADATA3") (class "Default")
      (node (ref "IC10") (pin "8") (pinfunction "4D_8") (pintype "input"))
      (node (ref "IC10") (pin "9") (pinfunction "4Q_9") (pintype "tri_state"))
      (node (ref "IC12") (pin "8") (pinfunction "4D_8") (pintype "input"))
      (node (ref "IC12") (pin "9") (pinfunction "4Q_9") (pintype "tri_state"))
      (node (ref "IC16") (pin "8") (pinfunction "4D_8") (pintype "input"))
      (node (ref "IC16") (pin "9") (pinfunction "4Q_9") (pintype "tri_state"))
      (node (ref "IC18") (pin "8") (pinfunction "4D_8") (pintype "input"))
      (node (ref "IC18") (pin "9") (pinfunction "4Q_9") (pintype "tri_state"))
      (node (ref "IC22") (pin "8") (pinfunction "4D_8") (pintype "input"))
      (node (ref "IC22") (pin "9") (pinfunction "4Q_9") (pintype "tri_state"))
      (node (ref "IC24") (pin "8") (pinfunction "4D_8") (pintype "input"))
      (node (ref "IC24") (pin "9") (pinfunction "4Q_9") (pintype "tri_state"))
      (node (ref "IC28") (pin "8") (pinfunction "4D_8") (pintype "input"))
      (node (ref "IC28") (pin "9") (pinfunction "4Q_9") (pintype "tri_state"))
      (node (ref "IC30") (pin "8") (pinfunction "4D_8") (pintype "input"))
      (node (ref "IC30") (pin "9") (pinfunction "4Q_9") (pintype "tri_state"))
      (node (ref "IC33") (pin "8") (pinfunction "A4_8") (pintype "input"))
      (node (ref "IC5") (pin "15") (pinfunction "B4_15") (pintype "bidirectional"))
      (node (ref "RN1") (pin "5") (pinfunction "1_5") (pintype "passive"))
    )
    (net (code "65") (name "ADATA4") (class "Default")
      (node (ref "IC10") (pin "12") (pinfunction "5Q_12") (pintype "tri_state"))
      (node (ref "IC10") (pin "13") (pinfunction "5D_13") (pintype "input"))
      (node (ref "IC12") (pin "12") (pinfunction "5Q_12") (pintype "tri_state"))
      (node (ref "IC12") (pin "13") (pinfunction "5D_13") (pintype "input"))
      (node (ref "IC16") (pin "12") (pinfunction "5Q_12") (pintype "tri_state"))
      (node (ref "IC16") (pin "13") (pinfunction "5D_13") (pintype "input"))
      (node (ref "IC18") (pin "12") (pinfunction "5Q_12") (pintype "tri_state"))
      (node (ref "IC18") (pin "13") (pinfunction "5D_13") (pintype "input"))
      (node (ref "IC22") (pin "12") (pinfunction "5Q_12") (pintype "tri_state"))
      (node (ref "IC22") (pin "13") (pinfunction "5D_13") (pintype "input"))
      (node (ref "IC24") (pin "12") (pinfunction "5Q_12") (pintype "tri_state"))
      (node (ref "IC24") (pin "13") (pinfunction "5D_13") (pintype "input"))
      (node (ref "IC28") (pin "12") (pinfunction "5Q_12") (pintype "tri_state"))
      (node (ref "IC28") (pin "13") (pinfunction "5D_13") (pintype "input"))
      (node (ref "IC30") (pin "12") (pinfunction "5Q_12") (pintype "tri_state"))
      (node (ref "IC30") (pin "13") (pinfunction "5D_13") (pintype "input"))
      (node (ref "IC33") (pin "11") (pinfunction "A1_11") (pintype "input"))
      (node (ref "IC5") (pin "14") (pinfunction "B5_14") (pintype "bidirectional"))
      (node (ref "RN1") (pin "6") (pinfunction "1_6") (pintype "passive"))
    )
    (net (code "66") (name "ADATA5") (class "Default")
      (node (ref "IC10") (pin "14") (pinfunction "6D_14") (pintype "input"))
      (node (ref "IC10") (pin "15") (pinfunction "6Q_15") (pintype "tri_state"))
      (node (ref "IC12") (pin "14") (pinfunction "6D_14") (pintype "input"))
      (node (ref "IC12") (pin "15") (pinfunction "6Q_15") (pintype "tri_state"))
      (node (ref "IC16") (pin "14") (pinfunction "6D_14") (pintype "input"))
      (node (ref "IC16") (pin "15") (pinfunction "6Q_15") (pintype "tri_state"))
      (node (ref "IC18") (pin "14") (pinfunction "6D_14") (pintype "input"))
      (node (ref "IC18") (pin "15") (pinfunction "6Q_15") (pintype "tri_state"))
      (node (ref "IC22") (pin "14") (pinfunction "6D_14") (pintype "input"))
      (node (ref "IC22") (pin "15") (pinfunction "6Q_15") (pintype "tri_state"))
      (node (ref "IC24") (pin "14") (pinfunction "6D_14") (pintype "input"))
      (node (ref "IC24") (pin "15") (pinfunction "6Q_15") (pintype "tri_state"))
      (node (ref "IC28") (pin "14") (pinfunction "6D_14") (pintype "input"))
      (node (ref "IC28") (pin "15") (pinfunction "6Q_15") (pintype "tri_state"))
      (node (ref "IC30") (pin "14") (pinfunction "6D_14") (pintype "input"))
      (node (ref "IC30") (pin "15") (pinfunction "6Q_15") (pintype "tri_state"))
      (node (ref "IC33") (pin "13") (pinfunction "A2_13") (pintype "input"))
      (node (ref "IC5") (pin "13") (pinfunction "B6_13") (pintype "bidirectional"))
      (node (ref "RN1") (pin "7") (pinfunction "1_7") (pintype "passive"))
    )
    (net (code "67") (name "ADATA6") (class "Default")
      (node (ref "IC10") (pin "16") (pinfunction "7Q_16") (pintype "tri_state"))
      (node (ref "IC10") (pin "17") (pinfunction "7D_17") (pintype "input"))
      (node (ref "IC12") (pin "16") (pinfunction "7Q_16") (pintype "tri_state"))
      (node (ref "IC12") (pin "17") (pinfunction "7D_17") (pintype "input"))
      (node (ref "IC16") (pin "16") (pinfunction "7Q_16") (pintype "tri_state"))
      (node (ref "IC16") (pin "17") (pinfunction "7D_17") (pintype "input"))
      (node (ref "IC18") (pin "16") (pinfunction "7Q_16") (pintype "tri_state"))
      (node (ref "IC18") (pin "17") (pinfunction "7D_17") (pintype "input"))
      (node (ref "IC22") (pin "16") (pinfunction "7Q_16") (pintype "tri_state"))
      (node (ref "IC22") (pin "17") (pinfunction "7D_17") (pintype "input"))
      (node (ref "IC24") (pin "16") (pinfunction "7Q_16") (pintype "tri_state"))
      (node (ref "IC24") (pin "17") (pinfunction "7D_17") (pintype "input"))
      (node (ref "IC28") (pin "16") (pinfunction "7Q_16") (pintype "tri_state"))
      (node (ref "IC28") (pin "17") (pinfunction "7D_17") (pintype "input"))
      (node (ref "IC30") (pin "16") (pinfunction "7Q_16") (pintype "tri_state"))
      (node (ref "IC30") (pin "17") (pinfunction "7D_17") (pintype "input"))
      (node (ref "IC33") (pin "15") (pinfunction "A3_15") (pintype "input"))
      (node (ref "IC5") (pin "12") (pinfunction "B7_12") (pintype "bidirectional"))
      (node (ref "RN1") (pin "8") (pinfunction "1_8") (pintype "passive"))
    )
    (net (code "68") (name "ADATA7") (class "Default")
      (node (ref "IC10") (pin "18") (pinfunction "8D_18") (pintype "input"))
      (node (ref "IC10") (pin "19") (pinfunction "8Q_19") (pintype "tri_state"))
      (node (ref "IC12") (pin "18") (pinfunction "8D_18") (pintype "input"))
      (node (ref "IC12") (pin "19") (pinfunction "8Q_19") (pintype "tri_state"))
      (node (ref "IC16") (pin "18") (pinfunction "8D_18") (pintype "input"))
      (node (ref "IC16") (pin "19") (pinfunction "8Q_19") (pintype "tri_state"))
      (node (ref "IC18") (pin "18") (pinfunction "8D_18") (pintype "input"))
      (node (ref "IC18") (pin "19") (pinfunction "8Q_19") (pintype "tri_state"))
      (node (ref "IC22") (pin "18") (pinfunction "8D_18") (pintype "input"))
      (node (ref "IC22") (pin "19") (pinfunction "8Q_19") (pintype "tri_state"))
      (node (ref "IC24") (pin "18") (pinfunction "8D_18") (pintype "input"))
      (node (ref "IC24") (pin "19") (pinfunction "8Q_19") (pintype "tri_state"))
      (node (ref "IC28") (pin "18") (pinfunction "8D_18") (pintype "input"))
      (node (ref "IC28") (pin "19") (pinfunction "8Q_19") (pintype "tri_state"))
      (node (ref "IC30") (pin "18") (pinfunction "8D_18") (pintype "input"))
      (node (ref "IC30") (pin "19") (pinfunction "8Q_19") (pintype "tri_state"))
      (node (ref "IC33") (pin "17") (pinfunction "A4_17") (pintype "input"))
      (node (ref "IC5") (pin "11") (pinfunction "B8_11") (pintype "bidirectional"))
      (node (ref "RN1") (pin "9") (pinfunction "1_9") (pintype "passive"))
    )
    (net (code "69") (name "ADATA8") (class "Default")
      (node (ref "IC11") (pin "2") (pinfunction "1Q_2") (pintype "tri_state"))
      (node (ref "IC11") (pin "3") (pinfunction "1D_3") (pintype "input"))
      (node (ref "IC13") (pin "2") (pinfunction "1Q_2") (pintype "tri_state"))
      (node (ref "IC13") (pin "3") (pinfunction "1D_3") (pintype "input"))
      (node (ref "IC17") (pin "2") (pinfunction "1Q_2") (pintype "tri_state"))
      (node (ref "IC17") (pin "3") (pinfunction "1D_3") (pintype "input"))
      (node (ref "IC19") (pin "2") (pinfunction "1Q_2") (pintype "tri_state"))
      (node (ref "IC19") (pin "3") (pinfunction "1D_3") (pintype "input"))
      (node (ref "IC23") (pin "2") (pinfunction "1Q_2") (pintype "tri_state"))
      (node (ref "IC23") (pin "3") (pinfunction "1D_3") (pintype "input"))
      (node (ref "IC25") (pin "2") (pinfunction "1Q_2") (pintype "tri_state"))
      (node (ref "IC25") (pin "3") (pinfunction "1D_3") (pintype "input"))
      (node (ref "IC29") (pin "2") (pinfunction "1Q_2") (pintype "tri_state"))
      (node (ref "IC29") (pin "3") (pinfunction "1D_3") (pintype "input"))
      (node (ref "IC31") (pin "2") (pinfunction "1Q_2") (pintype "tri_state"))
      (node (ref "IC31") (pin "3") (pinfunction "1D_3") (pintype "input"))
      (node (ref "IC32") (pin "2") (pinfunction "A1_2") (pintype "input"))
      (node (ref "IC6") (pin "18") (pinfunction "B1_18") (pintype "bidirectional"))
      (node (ref "IC7") (pin "18") (pinfunction "B1_18") (pintype "bidirectional"))
      (node (ref "RN2") (pin "2") (pinfunction "1_2") (pintype "passive"))
    )
    (net (code "70") (name "ADATA9") (class "Default")
      (node (ref "IC11") (pin "4") (pinfunction "2D_4") (pintype "input"))
      (node (ref "IC11") (pin "5") (pinfunction "2Q_5") (pintype "tri_state"))
      (node (ref "IC13") (pin "4") (pinfunction "2D_4") (pintype "input"))
      (node (ref "IC13") (pin "5") (pinfunction "2Q_5") (pintype "tri_state"))
      (node (ref "IC17") (pin "4") (pinfunction "2D_4") (pintype "input"))
      (node (ref "IC17") (pin "5") (pinfunction "2Q_5") (pintype "tri_state"))
      (node (ref "IC19") (pin "4") (pinfunction "2D_4") (pintype "input"))
      (node (ref "IC19") (pin "5") (pinfunction "2Q_5") (pintype "tri_state"))
      (node (ref "IC23") (pin "4") (pinfunction "2D_4") (pintype "input"))
      (node (ref "IC23") (pin "5") (pinfunction "2Q_5") (pintype "tri_state"))
      (node (ref "IC25") (pin "4") (pinfunction "2D_4") (pintype "input"))
      (node (ref "IC25") (pin "5") (pinfunction "2Q_5") (pintype "tri_state"))
      (node (ref "IC29") (pin "4") (pinfunction "2D_4") (pintype "input"))
      (node (ref "IC29") (pin "5") (pinfunction "2Q_5") (pintype "tri_state"))
      (node (ref "IC31") (pin "4") (pinfunction "2D_4") (pintype "input"))
      (node (ref "IC31") (pin "5") (pinfunction "2Q_5") (pintype "tri_state"))
      (node (ref "IC32") (pin "4") (pinfunction "A2_4") (pintype "input"))
      (node (ref "IC6") (pin "17") (pinfunction "B2_17") (pintype "bidirectional"))
      (node (ref "IC7") (pin "17") (pinfunction "B2_17") (pintype "bidirectional"))
      (node (ref "RN2") (pin "3") (pinfunction "1_3") (pintype "passive"))
    )
    (net (code "71") (name "ADATA10") (class "Default")
      (node (ref "IC11") (pin "6") (pinfunction "3Q_6") (pintype "tri_state"))
      (node (ref "IC11") (pin "7") (pinfunction "3D_7") (pintype "input"))
      (node (ref "IC13") (pin "6") (pinfunction "3Q_6") (pintype "tri_state"))
      (node (ref "IC13") (pin "7") (pinfunction "3D_7") (pintype "input"))
      (node (ref "IC17") (pin "6") (pinfunction "3Q_6") (pintype "tri_state"))
      (node (ref "IC17") (pin "7") (pinfunction "3D_7") (pintype "input"))
      (node (ref "IC19") (pin "6") (pinfunction "3Q_6") (pintype "tri_state"))
      (node (ref "IC19") (pin "7") (pinfunction "3D_7") (pintype "input"))
      (node (ref "IC23") (pin "6") (pinfunction "3Q_6") (pintype "tri_state"))
      (node (ref "IC23") (pin "7") (pinfunction "3D_7") (pintype "input"))
      (node (ref "IC25") (pin "6") (pinfunction "3Q_6") (pintype "tri_state"))
      (node (ref "IC25") (pin "7") (pinfunction "3D_7") (pintype "input"))
      (node (ref "IC29") (pin "6") (pinfunction "3Q_6") (pintype "tri_state"))
      (node (ref "IC29") (pin "7") (pinfunction "3D_7") (pintype "input"))
      (node (ref "IC31") (pin "6") (pinfunction "3Q_6") (pintype "tri_state"))
      (node (ref "IC31") (pin "7") (pinfunction "3D_7") (pintype "input"))
      (node (ref "IC32") (pin "6") (pinfunction "A3_6") (pintype "input"))
      (node (ref "IC6") (pin "16") (pinfunction "B3_16") (pintype "bidirectional"))
      (node (ref "IC7") (pin "16") (pinfunction "B3_16") (pintype "bidirectional"))
      (node (ref "RN2") (pin "4") (pinfunction "1_4") (pintype "passive"))
    )
    (net (code "72") (name "ADATA11") (class "Default")
      (node (ref "IC11") (pin "8") (pinfunction "4D_8") (pintype "input"))
      (node (ref "IC11") (pin "9") (pinfunction "4Q_9") (pintype "tri_state"))
      (node (ref "IC13") (pin "8") (pinfunction "4D_8") (pintype "input"))
      (node (ref "IC13") (pin "9") (pinfunction "4Q_9") (pintype "tri_state"))
      (node (ref "IC17") (pin "8") (pinfunction "4D_8") (pintype "input"))
      (node (ref "IC17") (pin "9") (pinfunction "4Q_9") (pintype "tri_state"))
      (node (ref "IC19") (pin "8") (pinfunction "4D_8") (pintype "input"))
      (node (ref "IC19") (pin "9") (pinfunction "4Q_9") (pintype "tri_state"))
      (node (ref "IC23") (pin "8") (pinfunction "4D_8") (pintype "input"))
      (node (ref "IC23") (pin "9") (pinfunction "4Q_9") (pintype "tri_state"))
      (node (ref "IC25") (pin "8") (pinfunction "4D_8") (pintype "input"))
      (node (ref "IC25") (pin "9") (pinfunction "4Q_9") (pintype "tri_state"))
      (node (ref "IC29") (pin "8") (pinfunction "4D_8") (pintype "input"))
      (node (ref "IC29") (pin "9") (pinfunction "4Q_9") (pintype "tri_state"))
      (node (ref "IC31") (pin "8") (pinfunction "4D_8") (pintype "input"))
      (node (ref "IC31") (pin "9") (pinfunction "4Q_9") (pintype "tri_state"))
      (node (ref "IC32") (pin "8") (pinfunction "A4_8") (pintype "input"))
      (node (ref "IC6") (pin "15") (pinfunction "B4_15") (pintype "bidirectional"))
      (node (ref "IC7") (pin "15") (pinfunction "B4_15") (pintype "bidirectional"))
      (node (ref "RN2") (pin "5") (pinfunction "1_5") (pintype "passive"))
    )
    (net (code "73") (name "ADATA12") (class "Default")
      (node (ref "IC11") (pin "12") (pinfunction "5Q_12") (pintype "tri_state"))
      (node (ref "IC11") (pin "13") (pinfunction "5D_13") (pintype "input"))
      (node (ref "IC13") (pin "12") (pinfunction "5Q_12") (pintype "tri_state"))
      (node (ref "IC13") (pin "13") (pinfunction "5D_13") (pintype "input"))
      (node (ref "IC17") (pin "12") (pinfunction "5Q_12") (pintype "tri_state"))
      (node (ref "IC17") (pin "13") (pinfunction "5D_13") (pintype "input"))
      (node (ref "IC19") (pin "12") (pinfunction "5Q_12") (pintype "tri_state"))
      (node (ref "IC19") (pin "13") (pinfunction "5D_13") (pintype "input"))
      (node (ref "IC23") (pin "12") (pinfunction "5Q_12") (pintype "tri_state"))
      (node (ref "IC23") (pin "13") (pinfunction "5D_13") (pintype "input"))
      (node (ref "IC25") (pin "12") (pinfunction "5Q_12") (pintype "tri_state"))
      (node (ref "IC25") (pin "13") (pinfunction "5D_13") (pintype "input"))
      (node (ref "IC29") (pin "12") (pinfunction "5Q_12") (pintype "tri_state"))
      (node (ref "IC29") (pin "13") (pinfunction "5D_13") (pintype "input"))
      (node (ref "IC31") (pin "12") (pinfunction "5Q_12") (pintype "tri_state"))
      (node (ref "IC31") (pin "13") (pinfunction "5D_13") (pintype "input"))
      (node (ref "IC32") (pin "11") (pinfunction "A1_11") (pintype "input"))
      (node (ref "IC6") (pin "14") (pinfunction "B5_14") (pintype "bidirectional"))
      (node (ref "IC7") (pin "14") (pinfunction "B5_14") (pintype "bidirectional"))
      (node (ref "RN2") (pin "6") (pinfunction "1_6") (pintype "passive"))
    )
    (net (code "74") (name "ADATA13") (class "Default")
      (node (ref "IC11") (pin "14") (pinfunction "6D_14") (pintype "input"))
      (node (ref "IC11") (pin "15") (pinfunction "6Q_15") (pintype "tri_state"))
      (node (ref "IC13") (pin "14") (pinfunction "6D_14") (pintype "input"))
      (node (ref "IC13") (pin "15") (pinfunction "6Q_15") (pintype "tri_state"))
      (node (ref "IC17") (pin "14") (pinfunction "6D_14") (pintype "input"))
      (node (ref "IC17") (pin "15") (pinfunction "6Q_15") (pintype "tri_state"))
      (node (ref "IC19") (pin "14") (pinfunction "6D_14") (pintype "input"))
      (node (ref "IC19") (pin "15") (pinfunction "6Q_15") (pintype "tri_state"))
      (node (ref "IC23") (pin "14") (pinfunction "6D_14") (pintype "input"))
      (node (ref "IC23") (pin "15") (pinfunction "6Q_15") (pintype "tri_state"))
      (node (ref "IC25") (pin "14") (pinfunction "6D_14") (pintype "input"))
      (node (ref "IC25") (pin "15") (pinfunction "6Q_15") (pintype "tri_state"))
      (node (ref "IC29") (pin "14") (pinfunction "6D_14") (pintype "input"))
      (node (ref "IC29") (pin "15") (pinfunction "6Q_15") (pintype "tri_state"))
      (node (ref "IC31") (pin "14") (pinfunction "6D_14") (pintype "input"))
      (node (ref "IC31") (pin "15") (pinfunction "6Q_15") (pintype "tri_state"))
      (node (ref "IC32") (pin "13") (pinfunction "A2_13") (pintype "input"))
      (node (ref "IC6") (pin "13") (pinfunction "B6_13") (pintype "bidirectional"))
      (node (ref "IC7") (pin "13") (pinfunction "B6_13") (pintype "bidirectional"))
      (node (ref "RN2") (pin "7") (pinfunction "1_7") (pintype "passive"))
    )
    (net (code "75") (name "ADATA14") (class "Default")
      (node (ref "IC11") (pin "16") (pinfunction "7Q_16") (pintype "tri_state"))
      (node (ref "IC11") (pin "17") (pinfunction "7D_17") (pintype "input"))
      (node (ref "IC13") (pin "16") (pinfunction "7Q_16") (pintype "tri_state"))
      (node (ref "IC13") (pin "17") (pinfunction "7D_17") (pintype "input"))
      (node (ref "IC17") (pin "16") (pinfunction "7Q_16") (pintype "tri_state"))
      (node (ref "IC17") (pin "17") (pinfunction "7D_17") (pintype "input"))
      (node (ref "IC19") (pin "16") (pinfunction "7Q_16") (pintype "tri_state"))
      (node (ref "IC19") (pin "17") (pinfunction "7D_17") (pintype "input"))
      (node (ref "IC23") (pin "16") (pinfunction "7Q_16") (pintype "tri_state"))
      (node (ref "IC23") (pin "17") (pinfunction "7D_17") (pintype "input"))
      (node (ref "IC25") (pin "16") (pinfunction "7Q_16") (pintype "tri_state"))
      (node (ref "IC25") (pin "17") (pinfunction "7D_17") (pintype "input"))
      (node (ref "IC29") (pin "16") (pinfunction "7Q_16") (pintype "tri_state"))
      (node (ref "IC29") (pin "17") (pinfunction "7D_17") (pintype "input"))
      (node (ref "IC31") (pin "16") (pinfunction "7Q_16") (pintype "tri_state"))
      (node (ref "IC31") (pin "17") (pinfunction "7D_17") (pintype "input"))
      (node (ref "IC32") (pin "15") (pinfunction "A3_15") (pintype "input"))
      (node (ref "IC6") (pin "12") (pinfunction "B7_12") (pintype "bidirectional"))
      (node (ref "IC7") (pin "12") (pinfunction "B7_12") (pintype "bidirectional"))
      (node (ref "RN2") (pin "8") (pinfunction "1_8") (pintype "passive"))
    )
    (net (code "76") (name "ADATA15") (class "Default")
      (node (ref "IC11") (pin "18") (pinfunction "8D_18") (pintype "input"))
      (node (ref "IC11") (pin "19") (pinfunction "8Q_19") (pintype "tri_state"))
      (node (ref "IC13") (pin "18") (pinfunction "8D_18") (pintype "input"))
      (node (ref "IC13") (pin "19") (pinfunction "8Q_19") (pintype "tri_state"))
      (node (ref "IC17") (pin "18") (pinfunction "8D_18") (pintype "input"))
      (node (ref "IC17") (pin "19") (pinfunction "8Q_19") (pintype "tri_state"))
      (node (ref "IC19") (pin "18") (pinfunction "8D_18") (pintype "input"))
      (node (ref "IC19") (pin "19") (pinfunction "8Q_19") (pintype "tri_state"))
      (node (ref "IC23") (pin "18") (pinfunction "8D_18") (pintype "input"))
      (node (ref "IC23") (pin "19") (pinfunction "8Q_19") (pintype "tri_state"))
      (node (ref "IC25") (pin "18") (pinfunction "8D_18") (pintype "input"))
      (node (ref "IC25") (pin "19") (pinfunction "8Q_19") (pintype "tri_state"))
      (node (ref "IC29") (pin "18") (pinfunction "8D_18") (pintype "input"))
      (node (ref "IC29") (pin "19") (pinfunction "8Q_19") (pintype "tri_state"))
      (node (ref "IC31") (pin "18") (pinfunction "8D_18") (pintype "input"))
      (node (ref "IC31") (pin "19") (pinfunction "8Q_19") (pintype "tri_state"))
      (node (ref "IC32") (pin "17") (pinfunction "A4_17") (pintype "input"))
      (node (ref "IC6") (pin "11") (pinfunction "B8_11") (pintype "bidirectional"))
      (node (ref "IC7") (pin "11") (pinfunction "B8_11") (pintype "bidirectional"))
      (node (ref "RN2") (pin "9") (pinfunction "1_9") (pintype "passive"))
    )
    (net (code "77") (name "ADDR0") (class "Default")
      (node (ref "X1") (pin "A3") (pinfunction "B_A3") (pintype "passive"))
    )
    (net (code "78") (name "ADDR1") (class "Default")
      (node (ref "X1") (pin "A4") (pinfunction "B_A4") (pintype "passive"))
    )
    (net (code "79") (name "ADDR2") (class "Default")
      (node (ref "X1") (pin "A5") (pinfunction "B_A5") (pintype "passive"))
    )
    (net (code "80") (name "ADDR3") (class "Default")
      (node (ref "X1") (pin "A6") (pinfunction "B_A6") (pintype "passive"))
    )
    (net (code "81") (name "ADDR4") (class "Default")
      (node (ref "X1") (pin "A7") (pinfunction "B_A7") (pintype "passive"))
    )
    (net (code "82") (name "ADDR5") (class "Default")
      (node (ref "X1") (pin "A8") (pinfunction "B_A8") (pintype "passive"))
    )
    (net (code "83") (name "ADDR6") (class "Default")
      (node (ref "X1") (pin "A9") (pinfunction "B_A9") (pintype "passive"))
    )
    (net (code "84") (name "ADDR7") (class "Default")
      (node (ref "X1") (pin "A10") (pinfunction "B_A10") (pintype "passive"))
    )
    (net (code "85") (name "ADDR8") (class "Default")
      (node (ref "X1") (pin "A11") (pinfunction "B_A11") (pintype "passive"))
    )
    (net (code "86") (name "ADDR9") (class "Default")
      (node (ref "X1") (pin "A12") (pinfunction "B_A12") (pintype "passive"))
    )
    (net (code "87") (name "ADDR10") (class "Default")
      (node (ref "X1") (pin "A13") (pinfunction "B_A13") (pintype "passive"))
    )
    (net (code "88") (name "ADDR11") (class "Default")
      (node (ref "X1") (pin "A14") (pinfunction "B_A14") (pintype "passive"))
    )
    (net (code "89") (name "ADDR12") (class "Default")
      (node (ref "X1") (pin "A15") (pinfunction "B_A15") (pintype "passive"))
    )
    (net (code "90") (name "ADDR13") (class "Default")
      (node (ref "X1") (pin "A16") (pinfunction "B_A16") (pintype "passive"))
    )
    (net (code "91") (name "ADDR14") (class "Default")
      (node (ref "X1") (pin "A17") (pinfunction "B_A17") (pintype "passive"))
    )
    (net (code "92") (name "ADDR15") (class "Default")
      (node (ref "X1") (pin "A18") (pinfunction "B_A18") (pintype "passive"))
    )
    (net (code "93") (name "ALU0") (class "Default")
      (node (ref "X1") (pin "C16") (pinfunction "B_C16") (pintype "passive"))
    )
    (net (code "94") (name "ALU1") (class "Default")
      (node (ref "X1") (pin "C17") (pinfunction "B_C17") (pintype "passive"))
    )
    (net (code "95") (name "ALU2") (class "Default")
      (node (ref "X1") (pin "C18") (pinfunction "B_C18") (pintype "passive"))
    )
    (net (code "96") (name "ALU3") (class "Default")
      (node (ref "X1") (pin "C19") (pinfunction "B_C19") (pintype "passive"))
    )
    (net (code "97") (name "BR-COND") (class "Default")
      (node (ref "X1") (pin "C24") (pinfunction "B_C24") (pintype "passive"))
    )
    (net (code "98") (name "BUS-DIR") (class "Default")
      (node (ref "IC2") (pin "11") (pinfunction "O_11") (pintype "output"))
      (node (ref "IC5") (pin "1") (pinfunction "DIR_1") (pintype "input"))
      (node (ref "IC6") (pin "1") (pinfunction "DIR_1") (pintype "input"))
      (node (ref "IC7") (pin "1") (pinfunction "DIR_1") (pintype "input"))
    )
    (net (code "99") (name "CLK0H") (class "Default")
      (node (ref "IC11") (pin "11") (pinfunction "CLK_11") (pintype "input"))
      (node (ref "IC35") (pin "15") (pinfunction "A3_15") (pintype "input"))
      (node (ref "IC9") (pin "4") (pinfunction "O_4") (pintype "output"))
    )
    (net (code "100") (name "CLK0L") (class "Default")
      (node (ref "IC10") (pin "11") (pinfunction "CLK_11") (pintype "input"))
      (node (ref "IC35") (pin "17") (pinfunction "A4_17") (pintype "input"))
      (node (ref "IC9") (pin "1") (pinfunction "O_1") (pintype "output"))
    )
    (net (code "101") (name "CLK1H") (class "Default")
      (node (ref "IC13") (pin "11") (pinfunction "CLK_11") (pintype "input"))
      (node (ref "IC35") (pin "11") (pinfunction "A1_11") (pintype "input"))
      (node (ref "IC9") (pin "13") (pinfunction "O_13") (pintype "output"))
    )
    (net (code "102") (name "CLK1L") (class "Default")
      (node (ref "IC12") (pin "11") (pinfunction "CLK_11") (pintype "input"))
      (node (ref "IC35") (pin "13") (pinfunction "A2_13") (pintype "input"))
      (node (ref "IC9") (pin "10") (pinfunction "O_10") (pintype "output"))
    )
    (net (code "103") (name "CLK2H") (class "Default")
      (node (ref "IC15") (pin "4") (pinfunction "O_4") (pintype "output"))
      (node (ref "IC17") (pin "11") (pinfunction "CLK_11") (pintype "input"))
      (node (ref "IC34") (pin "4") (pinfunction "A2_4") (pintype "input"))
    )
    (net (code "104") (name "CLK2L") (class "Default")
      (node (ref "IC15") (pin "1") (pinfunction "O_1") (pintype "output"))
      (node (ref "IC16") (pin "11") (pinfunction "CLK_11") (pintype "input"))
      (node (ref "IC34") (pin "2") (pinfunction "A1_2") (pintype "input"))
    )
    (net (code "105") (name "CLK3H") (class "Default")
      (node (ref "IC15") (pin "13") (pinfunction "O_13") (pintype "output"))
      (node (ref "IC19") (pin "11") (pinfunction "CLK_11") (pintype "input"))
      (node (ref "IC34") (pin "8") (pinfunction "A4_8") (pintype "input"))
    )
    (net (code "106") (name "CLK3L") (class "Default")
      (node (ref "IC15") (pin "10") (pinfunction "O_10") (pintype "output"))
      (node (ref "IC18") (pin "11") (pinfunction "CLK_11") (pintype "input"))
      (node (ref "IC34") (pin "6") (pinfunction "A3_6") (pintype "input"))
    )
    (net (code "107") (name "CLK4H") (class "Default")
      (node (ref "IC21") (pin "4") (pinfunction "O_4") (pintype "output"))
      (node (ref "IC23") (pin "11") (pinfunction "CLK_11") (pintype "input"))
      (node (ref "IC35") (pin "6") (pinfunction "A3_6") (pintype "input"))
    )
    (net (code "108") (name "CLK4L") (class "Default")
      (node (ref "IC21") (pin "1") (pinfunction "O_1") (pintype "output"))
      (node (ref "IC22") (pin "11") (pinfunction "CLK_11") (pintype "input"))
      (node (ref "IC35") (pin "8") (pinfunction "A4_8") (pintype "input"))
    )
    (net (code "109") (name "CLK5H") (class "Default")
      (node (ref "IC21") (pin "13") (pinfunction "O_13") (pintype "output"))
      (node (ref "IC25") (pin "11") (pinfunction "CLK_11") (pintype "input"))
      (node (ref "IC35") (pin "2") (pinfunction "A1_2") (pintype "input"))
    )
    (net (code "110") (name "CLK5L") (class "Default")
      (node (ref "IC21") (pin "10") (pinfunction "O_10") (pintype "output"))
      (node (ref "IC24") (pin "11") (pinfunction "CLK_11") (pintype "input"))
      (node (ref "IC35") (pin "4") (pinfunction "A2_4") (pintype "input"))
    )
    (net (code "111") (name "CLK6H") (class "Default")
      (node (ref "IC27") (pin "4") (pinfunction "O_4") (pintype "output"))
      (node (ref "IC29") (pin "11") (pinfunction "CLK_11") (pintype "input"))
      (node (ref "IC34") (pin "13") (pinfunction "A2_13") (pintype "input"))
    )
    (net (code "112") (name "CLK6L") (class "Default")
      (node (ref "IC27") (pin "1") (pinfunction "O_1") (pintype "output"))
      (node (ref "IC28") (pin "11") (pinfunction "CLK_11") (pintype "input"))
      (node (ref "IC34") (pin "11") (pinfunction "A1_11") (pintype "input"))
    )
    (net (code "113") (name "CLK7H") (class "Default")
      (node (ref "IC27") (pin "13") (pinfunction "O_13") (pintype "output"))
      (node (ref "IC31") (pin "11") (pinfunction "CLK_11") (pintype "input"))
      (node (ref "IC34") (pin "17") (pinfunction "A4_17") (pintype "input"))
    )
    (net (code "114") (name "CLK7L") (class "Default")
      (node (ref "IC27") (pin "10") (pinfunction "O_10") (pintype "output"))
      (node (ref "IC30") (pin "11") (pinfunction "CLK_11") (pintype "input"))
      (node (ref "IC34") (pin "15") (pinfunction "A3_15") (pintype "input"))
    )
    (net (code "115") (name "DATA0") (class "Default")
      (node (ref "IC5") (pin "2") (pinfunction "A1_2") (pintype "bidirectional"))
      (node (ref "IC7") (pin "2") (pinfunction "A1_2") (pintype "bidirectional"))
      (node (ref "X1") (pin "A19") (pinfunction "B_A19") (pintype "passive"))
    )
    (net (code "116") (name "DATA1") (class "Default")
      (node (ref "IC5") (pin "3") (pinfunction "A2_3") (pintype "bidirectional"))
      (node (ref "IC7") (pin "3") (pinfunction "A2_3") (pintype "bidirectional"))
      (node (ref "X1") (pin "A20") (pinfunction "B_A20") (pintype "passive"))
    )
    (net (code "117") (name "DATA2") (class "Default")
      (node (ref "IC5") (pin "4") (pinfunction "A3_4") (pintype "bidirectional"))
      (node (ref "IC7") (pin "4") (pinfunction "A3_4") (pintype "bidirectional"))
      (node (ref "X1") (pin "A21") (pinfunction "B_A21") (pintype "passive"))
    )
    (net (code "118") (name "DATA3") (class "Default")
      (node (ref "IC5") (pin "5") (pinfunction "A4_5") (pintype "bidirectional"))
      (node (ref "IC7") (pin "5") (pinfunction "A4_5") (pintype "bidirectional"))
      (node (ref "X1") (pin "A22") (pinfunction "B_A22") (pintype "passive"))
    )
    (net (code "119") (name "DATA4") (class "Default")
      (node (ref "IC5") (pin "6") (pinfunction "A5_6") (pintype "bidirectional"))
      (node (ref "IC7") (pin "6") (pinfunction "A5_6") (pintype "bidirectional"))
      (node (ref "X1") (pin "A23") (pinfunction "B_A23") (pintype "passive"))
    )
    (net (code "120") (name "DATA5") (class "Default")
      (node (ref "IC5") (pin "7") (pinfunction "A6_7") (pintype "bidirectional"))
      (node (ref "IC7") (pin "7") (pinfunction "A6_7") (pintype "bidirectional"))
      (node (ref "X1") (pin "A24") (pinfunction "B_A24") (pintype "passive"))
    )
    (net (code "121") (name "DATA6") (class "Default")
      (node (ref "IC5") (pin "8") (pinfunction "A7_8") (pintype "bidirectional"))
      (node (ref "IC7") (pin "8") (pinfunction "A7_8") (pintype "bidirectional"))
      (node (ref "X1") (pin "A25") (pinfunction "B_A25") (pintype "passive"))
    )
    (net (code "122") (name "DATA7") (class "Default")
      (node (ref "IC5") (pin "9") (pinfunction "A8_9") (pintype "bidirectional"))
      (node (ref "IC7") (pin "9") (pinfunction "A8_9") (pintype "bidirectional"))
      (node (ref "X1") (pin "A26") (pinfunction "B_A26") (pintype "passive"))
    )
    (net (code "123") (name "DATA8") (class "Default")
      (node (ref "IC6") (pin "2") (pinfunction "A1_2") (pintype "bidirectional"))
      (node (ref "X1") (pin "A27") (pinfunction "B_A27") (pintype "passive"))
    )
    (net (code "124") (name "DATA9") (class "Default")
      (node (ref "IC6") (pin "3") (pinfunction "A2_3") (pintype "bidirectional"))
      (node (ref "X1") (pin "A28") (pinfunction "B_A28") (pintype "passive"))
    )
    (net (code "125") (name "DATA10") (class "Default")
      (node (ref "IC6") (pin "4") (pinfunction "A3_4") (pintype "bidirectional"))
      (node (ref "X1") (pin "A29") (pinfunction "B_A29") (pintype "passive"))
    )
    (net (code "126") (name "DATA11") (class "Default")
      (node (ref "IC6") (pin "5") (pinfunction "A4_5") (pintype "bidirectional"))
      (node (ref "X1") (pin "A30") (pinfunction "B_A30") (pintype "passive"))
    )
    (net (code "127") (name "DATA12") (class "Default")
      (node (ref "IC6") (pin "6") (pinfunction "A5_6") (pintype "bidirectional"))
      (node (ref "X1") (pin "B3") (pinfunction "B_B3") (pintype "passive"))
    )
    (net (code "128") (name "DATA13") (class "Default")
      (node (ref "IC6") (pin "7") (pinfunction "A6_7") (pintype "bidirectional"))
      (node (ref "X1") (pin "B4") (pinfunction "B_B4") (pintype "passive"))
    )
    (net (code "129") (name "DATA14") (class "Default")
      (node (ref "IC6") (pin "8") (pinfunction "A7_8") (pintype "bidirectional"))
      (node (ref "X1") (pin "B5") (pinfunction "B_B5") (pintype "passive"))
    )
    (net (code "130") (name "DATA15") (class "Default")
      (node (ref "IC6") (pin "9") (pinfunction "A8_9") (pintype "bidirectional"))
      (node (ref "X1") (pin "B6") (pinfunction "B_B6") (pintype "passive"))
    )
    (net (code "131") (name "FP-ADATA0") (class "Default")
      (node (ref "IC33") (pin "18") (pinfunction "Y1_18") (pintype "tri_state"))
      (node (ref "JP1") (pin "3") (pinfunction "3_3") (pintype "passive"))
    )
    (net (code "132") (name "FP-ADATA1") (class "Default")
      (node (ref "IC33") (pin "16") (pinfunction "Y2_16") (pintype "tri_state"))
      (node (ref "JP1") (pin "5") (pinfunction "5_5") (pintype "passive"))
    )
    (net (code "133") (name "FP-ADATA2") (class "Default")
      (node (ref "IC33") (pin "14") (pinfunction "Y3_14") (pintype "tri_state"))
      (node (ref "JP1") (pin "7") (pinfunction "7_7") (pintype "passive"))
    )
    (net (code "134") (name "FP-ADATA3") (class "Default")
      (node (ref "IC33") (pin "12") (pinfunction "Y4_12") (pintype "tri_state"))
      (node (ref "JP1") (pin "9") (pinfunction "9_9") (pintype "passive"))
    )
    (net (code "135") (name "FP-ADATA4") (class "Default")
      (node (ref "IC33") (pin "9") (pinfunction "Y1_9") (pintype "tri_state"))
      (node (ref "JP1") (pin "11") (pinfunction "11_11") (pintype "passive"))
    )
    (net (code "136") (name "FP-ADATA5") (class "Default")
      (node (ref "IC33") (pin "7") (pinfunction "Y2_7") (pintype "tri_state"))
      (node (ref "JP1") (pin "13") (pinfunction "13_13") (pintype "passive"))
    )
    (net (code "137") (name "FP-ADATA6") (class "Default")
      (node (ref "IC33") (pin "5") (pinfunction "Y3_5") (pintype "tri_state"))
      (node (ref "JP1") (pin "15") (pinfunction "15_15") (pintype "passive"))
    )
    (net (code "138") (name "FP-ADATA7") (class "Default")
      (node (ref "IC33") (pin "3") (pinfunction "Y4_3") (pintype "tri_state"))
      (node (ref "JP1") (pin "17") (pinfunction "17_17") (pintype "passive"))
    )
    (net (code "139") (name "FP-ADATA8") (class "Default")
      (node (ref "IC32") (pin "18") (pinfunction "Y1_18") (pintype "tri_state"))
      (node (ref "JP1") (pin "4") (pinfunction "4_4") (pintype "passive"))
    )
    (net (code "140") (name "FP-ADATA9") (class "Default")
      (node (ref "IC32") (pin "16") (pinfunction "Y2_16") (pintype "tri_state"))
      (node (ref "JP1") (pin "6") (pinfunction "6_6") (pintype "passive"))
    )
    (net (code "141") (name "FP-ADATA10") (class "Default")
      (node (ref "IC32") (pin "14") (pinfunction "Y3_14") (pintype "tri_state"))
      (node (ref "JP1") (pin "8") (pinfunction "8_8") (pintype "passive"))
    )
    (net (code "142") (name "FP-ADATA11") (class "Default")
      (node (ref "IC32") (pin "12") (pinfunction "Y4_12") (pintype "tri_state"))
      (node (ref "JP1") (pin "10") (pinfunction "10_10") (pintype "passive"))
    )
    (net (code "143") (name "FP-ADATA12") (class "Default")
      (node (ref "IC32") (pin "9") (pinfunction "Y1_9") (pintype "tri_state"))
      (node (ref "JP1") (pin "12") (pinfunction "12_12") (pintype "passive"))
    )
    (net (code "144") (name "FP-ADATA13") (class "Default")
      (node (ref "IC32") (pin "7") (pinfunction "Y2_7") (pintype "tri_state"))
      (node (ref "JP1") (pin "14") (pinfunction "14_14") (pintype "passive"))
    )
    (net (code "145") (name "FP-ADATA14") (class "Default")
      (node (ref "IC32") (pin "5") (pinfunction "Y3_5") (pintype "tri_state"))
      (node (ref "JP1") (pin "16") (pinfunction "16_16") (pintype "passive"))
    )
    (net (code "146") (name "FP-ADATA15") (class "Default")
      (node (ref "IC32") (pin "3") (pinfunction "Y4_3") (pintype "tri_state"))
      (node (ref "JP1") (pin "18") (pinfunction "18_18") (pintype "passive"))
    )
    (net (code "147") (name "FP-CLK0H") (class "Default")
      (node (ref "IC35") (pin "5") (pinfunction "Y3_5") (pintype "tri_state"))
      (node (ref "JP1") (pin "23") (pinfunction "23_23") (pintype "passive"))
    )
    (net (code "148") (name "FP-CLK0L") (class "Default")
      (node (ref "IC35") (pin "3") (pinfunction "Y4_3") (pintype "tri_state"))
      (node (ref "JP1") (pin "25") (pinfunction "25_25") (pintype "passive"))
    )
    (net (code "149") (name "FP-CLK1H") (class "Default")
      (node (ref "IC35") (pin "9") (pinfunction "Y1_9") (pintype "tri_state"))
      (node (ref "JP1") (pin "19") (pinfunction "19_19") (pintype "passive"))
    )
    (net (code "150") (name "FP-CLK1L") (class "Default")
      (node (ref "IC35") (pin "7") (pinfunction "Y2_7") (pintype "tri_state"))
      (node (ref "JP1") (pin "21") (pinfunction "21_21") (pintype "passive"))
    )
    (net (code "151") (name "FP-CLK2H") (class "Default")
      (node (ref "IC34") (pin "16") (pinfunction "Y2_16") (pintype "tri_state"))
      (node (ref "JP1") (pin "24") (pinfunction "24_24") (pintype "passive"))
    )
    (net (code "152") (name "FP-CLK2L") (class "Default")
      (node (ref "IC34") (pin "18") (pinfunction "Y1_18") (pintype "tri_state"))
      (node (ref "JP1") (pin "26") (pinfunction "26_26") (pintype "passive"))
    )
    (net (code "153") (name "FP-CLK3H") (class "Default")
      (node (ref "IC34") (pin "12") (pinfunction "Y4_12") (pintype "tri_state"))
      (node (ref "JP1") (pin "20") (pinfunction "20_20") (pintype "passive"))
    )
    (net (code "154") (name "FP-CLK3L") (class "Default")
      (node (ref "IC34") (pin "14") (pinfunction "Y3_14") (pintype "tri_state"))
      (node (ref "JP1") (pin "22") (pinfunction "22_22") (pintype "passive"))
    )
    (net (code "155") (name "FP-CLK4H") (class "Default")
      (node (ref "IC35") (pin "14") (pinfunction "Y3_14") (pintype "tri_state"))
      (node (ref "JP1") (pin "31") (pinfunction "31_31") (pintype "passive"))
    )
    (net (code "156") (name "FP-CLK4L") (class "Default")
      (node (ref "IC35") (pin "12") (pinfunction "Y4_12") (pintype "tri_state"))
      (node (ref "JP1") (pin "33") (pinfunction "33_33") (pintype "passive"))
    )
    (net (code "157") (name "FP-CLK5H") (class "Default")
      (node (ref "IC35") (pin "18") (pinfunction "Y1_18") (pintype "tri_state"))
      (node (ref "JP1") (pin "27") (pinfunction "27_27") (pintype "passive"))
    )
    (net (code "158") (name "FP-CLK5L") (class "Default")
      (node (ref "IC35") (pin "16") (pinfunction "Y2_16") (pintype "tri_state"))
      (node (ref "JP1") (pin "29") (pinfunction "29_29") (pintype "passive"))
    )
    (net (code "159") (name "FP-CLK6H") (class "Default")
      (node (ref "IC34") (pin "7") (pinfunction "Y2_7") (pintype "tri_state"))
      (node (ref "JP1") (pin "32") (pinfunction "32_32") (pintype "passive"))
    )
    (net (code "160") (name "FP-CLK6L") (class "Default")
      (node (ref "IC34") (pin "9") (pinfunction "Y1_9") (pintype "tri_state"))
      (node (ref "JP1") (pin "34") (pinfunction "34_34") (pintype "passive"))
    )
    (net (code "161") (name "FP-CLK7H") (class "Default")
      (node (ref "IC34") (pin "3") (pinfunction "Y4_3") (pintype "tri_state"))
      (node (ref "JP1") (pin "28") (pinfunction "28_28") (pintype "passive"))
    )
    (net (code "162") (name "FP-CLK7L") (class "Default")
      (node (ref "IC34") (pin "5") (pinfunction "Y3_5") (pintype "tri_state"))
      (node (ref "JP1") (pin "30") (pinfunction "30_30") (pintype "passive"))
    )
    (net (code "163") (name "GND") (class "Default")
      (node (ref "C1") (pin "2") (pinfunction "2_2") (pintype "passive"))
      (node (ref "C10") (pin "2") (pinfunction "2_2") (pintype "passive"))
      (node (ref "C11") (pin "2") (pinfunction "2_2") (pintype "passive"))
      (node (ref "C12") (pin "2") (pinfunction "2_2") (pintype "passive"))
      (node (ref "C13") (pin "2") (pinfunction "2_2") (pintype "passive"))
      (node (ref "C14") (pin "2") (pinfunction "2_2") (pintype "passive"))
      (node (ref "C15") (pin "2") (pinfunction "2_2") (pintype "passive"))
      (node (ref "C16") (pin "2") (pinfunction "2_2") (pintype "passive"))
      (node (ref "C17") (pin "2") (pinfunction "2_2") (pintype "passive"))
      (node (ref "C18") (pin "2") (pinfunction "2_2") (pintype "passive"))
      (node (ref "C19") (pin "2") (pinfunction "2_2") (pintype "passive"))
      (node (ref "C2") (pin "2") (pinfunction "2_2") (pintype "passive"))
      (node (ref "C20") (pin "2") (pinfunction "2_2") (pintype "passive"))
      (node (ref "C21") (pin "2") (pinfunction "2_2") (pintype "passive"))
      (node (ref "C22") (pin "2") (pinfunction "2_2") (pintype "passive"))
      (node (ref "C23") (pin "2") (pinfunction "2_2") (pintype "passive"))
      (node (ref "C24") (pin "2") (pinfunction "2_2") (pintype "passive"))
      (node (ref "C25") (pin "2") (pinfunction "2_2") (pintype "passive"))
      (node (ref "C26") (pin "2") (pinfunction "2_2") (pintype "passive"))
      (node (ref "C27") (pin "2") (pinfunction "2_2") (pintype "passive"))
      (node (ref "C28") (pin "2") (pinfunction "2_2") (pintype "passive"))
      (node (ref "C29") (pin "2") (pinfunction "2_2") (pintype "passive"))
      (node (ref "C3") (pin "2") (pinfunction "2_2") (pintype "passive"))
      (node (ref "C30") (pin "2") (pinfunction "2_2") (pintype "passive"))
      (node (ref "C31") (pin "2") (pinfunction "2_2") (pintype "passive"))
      (node (ref "C32") (pin "2") (pinfunction "2_2") (pintype "passive"))
      (node (ref "C33") (pin "2") (pinfunction "2_2") (pintype "passive"))
      (node (ref "C34") (pin "2") (pinfunction "2_2") (pintype "passive"))
      (node (ref "C35") (pin "2") (pinfunction "2_2") (pintype "passive"))
      (node (ref "C36") (pin "2") (pinfunction "2_2") (pintype "passive"))
      (node (ref "C37") (pin "2") (pinfunction "2_2") (pintype "passive"))
      (node (ref "C38") (pin "2") (pinfunction "2_2") (pintype "passive"))
      (node (ref "C4") (pin "2") (pinfunction "2_2") (pintype "passive"))
      (node (ref "C5") (pin "2") (pinfunction "2_2") (pintype "passive"))
      (node (ref "C6") (pin "2") (pinfunction "2_2") (pintype "passive"))
      (node (ref "C7") (pin "2") (pinfunction "2_2") (pintype "passive"))
      (node (ref "C8") (pin "2") (pinfunction "2_2") (pintype "passive"))
      (node (ref "C9") (pin "2") (pinfunction "2_2") (pintype "passive"))
      (node (ref "IC1") (pin "5") (pinfunction "I0_5") (pintype "input"))
      (node (ref "IC1") (pin "6") (pinfunction "I1_6") (pintype "input"))
      (node (ref "IC2") (pin "1") (pinfunction "I0_1") (pintype "input"))
      (node (ref "IC2") (pin "2") (pinfunction "I1_2") (pintype "input"))
      (node (ref "IC2") (pin "4") (pinfunction "I0_4") (pintype "input"))
      (node (ref "IC2") (pin "5") (pinfunction "I1_5") (pintype "input"))
      (node (ref "IC40") (pin "11") (pinfunction "I_11") (pintype "input"))
      (node (ref "IC40") (pin "13") (pinfunction "I_13") (pintype "input"))
      (node (ref "J1") (pin "2") (pinfunction "2_2") (pintype "passive"))
      (node (ref "JP1") (pin "39") (pinfunction "39_39") (pintype "passive"))
      (node (ref "JP1") (pin "40") (pinfunction "40_40") (pintype "passive"))
      (node (ref "PWR") (pin "K") (pinfunction "C_K") (pintype "passive"))
      (node (ref "X1") (pin "A1") (pinfunction "B_A1") (pintype "passive"))
      (node (ref "X1") (pin "A32") (pinfunction "B_A32") (pintype "passive"))
      (node (ref "X1") (pin "B1") (pinfunction "B_B1") (pintype "passive"))
      (node (ref "X1") (pin "B32") (pinfunction "B_B32") (pintype "passive"))
      (node (ref "X1") (pin "C1") (pinfunction "B_C1") (pintype "passive"))
      (node (ref "X1") (pin "C32") (pinfunction "B_C32") (pintype "passive"))
    )
    (net (code "164") (name "IO-ADDR0") (class "Default")
      (node (ref "X1") (pin "C7") (pinfunction "B_C7") (pintype "passive"))
    )
    (net (code "165") (name "IO-ADDR1") (class "Default")
      (node (ref "X1") (pin "C8") (pinfunction "B_C8") (pintype "passive"))
    )
    (net (code "166") (name "IO-ADDR2") (class "Default")
      (node (ref "X1") (pin "C9") (pinfunction "B_C9") (pintype "passive"))
    )
    (net (code "167") (name "IO-ADDR3") (class "Default")
      (node (ref "X1") (pin "C10") (pinfunction "B_C10") (pintype "passive"))
    )
    (net (code "168") (name "Net-(IC1C-O)") (class "Default")
      (node (ref "IC1") (pin "10") (pinfunction "O_10") (pintype "open_collector"))
      (node (ref "IC39") (pin "10") (pinfunction "I1_10") (pintype "input"))
      (node (ref "IC39") (pin "12") (pinfunction "I0_12") (pintype "input"))
    )
    (net (code "169") (name "Net-(IC2C-O)") (class "Default")
      (node (ref "IC2") (pin "8") (pinfunction "O_8") (pintype "output"))
      (node (ref "IC39") (pin "9") (pinfunction "I0_9") (pintype "input"))
    )
    (net (code "170") (name "Net-(IC10A-OC)") (class "Default")
      (node (ref "IC10") (pin "1") (pinfunction "OC_1") (pintype "input"))
      (node (ref "IC8") (pin "3") (pinfunction "O_3") (pintype "output"))
    )
    (net (code "171") (name "Net-(IC11A-OC)") (class "Default")
      (node (ref "IC11") (pin "1") (pinfunction "OC_1") (pintype "input"))
      (node (ref "IC8") (pin "6") (pinfunction "O_6") (pintype "output"))
    )
    (net (code "172") (name "Net-(IC12A-OC)") (class "Default")
      (node (ref "IC12") (pin "1") (pinfunction "OC_1") (pintype "input"))
      (node (ref "IC8") (pin "8") (pinfunction "O_8") (pintype "output"))
    )
    (net (code "173") (name "Net-(IC13A-OC)") (class "Default")
      (node (ref "IC13") (pin "1") (pinfunction "OC_1") (pintype "input"))
      (node (ref "IC8") (pin "11") (pinfunction "O_11") (pintype "output"))
    )
    (net (code "174") (name "Net-(IC14A-O)") (class "Default")
      (node (ref "IC14") (pin "3") (pinfunction "O_3") (pintype "output"))
      (node (ref "IC16") (pin "1") (pinfunction "OC_1") (pintype "input"))
    )
    (net (code "175") (name "Net-(IC14B-O)") (class "Default")
      (node (ref "IC14") (pin "6") (pinfunction "O_6") (pintype "output"))
      (node (ref "IC17") (pin "1") (pinfunction "OC_1") (pintype "input"))
    )
    (net (code "176") (name "Net-(IC14C-O)") (class "Default")
      (node (ref "IC14") (pin "8") (pinfunction "O_8") (pintype "output"))
      (node (ref "IC18") (pin "1") (pinfunction "OC_1") (pintype "input"))
    )
    (net (code "177") (name "Net-(IC14D-O)") (class "Default")
      (node (ref "IC14") (pin "11") (pinfunction "O_11") (pintype "output"))
      (node (ref "IC19") (pin "1") (pinfunction "OC_1") (pintype "input"))
    )
    (net (code "178") (name "Net-(IC20A-O)") (class "Default")
      (node (ref "IC20") (pin "3") (pinfunction "O_3") (pintype "output"))
      (node (ref "IC22") (pin "1") (pinfunction "OC_1") (pintype "input"))
    )
    (net (code "179") (name "Net-(IC20B-O)") (class "Default")
      (node (ref "IC20") (pin "6") (pinfunction "O_6") (pintype "output"))
      (node (ref "IC23") (pin "1") (pinfunction "OC_1") (pintype "input"))
    )
    (net (code "180") (name "Net-(IC20C-O)") (class "Default")
      (node (ref "IC20") (pin "8") (pinfunction "O_8") (pintype "output"))
      (node (ref "IC24") (pin "1") (pinfunction "OC_1") (pintype "input"))
    )
    (net (code "181") (name "Net-(IC20D-O)") (class "Default")
      (node (ref "IC20") (pin "11") (pinfunction "O_11") (pintype "output"))
      (node (ref "IC25") (pin "1") (pinfunction "OC_1") (pintype "input"))
    )
    (net (code "182") (name "Net-(IC26A-O)") (class "Default")
      (node (ref "IC26") (pin "3") (pinfunction "O_3") (pintype "output"))
      (node (ref "IC28") (pin "1") (pinfunction "OC_1") (pintype "input"))
    )
    (net (code "183") (name "Net-(IC26B-O)") (class "Default")
      (node (ref "IC26") (pin "6") (pinfunction "O_6") (pintype "output"))
      (node (ref "IC29") (pin "1") (pinfunction "OC_1") (pintype "input"))
    )
    (net (code "184") (name "Net-(IC26C-O)") (class "Default")
      (node (ref "IC26") (pin "8") (pinfunction "O_8") (pintype "output"))
      (node (ref "IC30") (pin "1") (pinfunction "OC_1") (pintype "input"))
    )
    (net (code "185") (name "Net-(IC26D-O)") (class "Default")
      (node (ref "IC26") (pin "11") (pinfunction "O_11") (pintype "output"))
      (node (ref "IC31") (pin "1") (pinfunction "OC_1") (pintype "input"))
    )
    (net (code "186") (name "Net-(IC32A-G)") (class "Default")
      (node (ref "IC32") (pin "1") (pinfunction "G_1") (pintype "input"))
      (node (ref "IC32") (pin "19") (pinfunction "G_19") (pintype "input"))
      (node (ref "IC33") (pin "1") (pinfunction "G_1") (pintype "input"))
      (node (ref "IC33") (pin "19") (pinfunction "G_19") (pintype "input"))
      (node (ref "IC34") (pin "1") (pinfunction "G_1") (pintype "input"))
      (node (ref "IC34") (pin "19") (pinfunction "G_19") (pintype "input"))
      (node (ref "IC35") (pin "1") (pinfunction "G_1") (pintype "input"))
      (node (ref "IC35") (pin "19") (pinfunction "G_19") (pintype "input"))
      (node (ref "J1") (pin "1") (pinfunction "1_1") (pintype "passive"))
      (node (ref "R1") (pin "1") (pinfunction "1_1") (pintype "passive"))
    )
    (net (code "187") (name "Net-(IC36A-G)") (class "Default")
      (node (ref "IC36") (pin "1") (pinfunction "G_1") (pintype "input"))
      (node (ref "IC39") (pin "3") (pinfunction "O_3") (pintype "output"))
    )
    (net (code "188") (name "Net-(IC36A-Y0)") (class "Default")
      (node (ref "IC36") (pin "4") (pinfunction "Y0_4") (pintype "output"))
      (node (ref "J2") (pin "1") (pinfunction "1_1") (pintype "passive"))
      (node (ref "J3") (pin "1") (pinfunction "1_1") (pintype "passive"))
    )
    (net (code "189") (name "Net-(IC36A-Y1)") (class "Default")
      (node (ref "IC36") (pin "5") (pinfunction "Y1_5") (pintype "output"))
      (node (ref "J2") (pin "3") (pinfunction "3_3") (pintype "passive"))
      (node (ref "J3") (pin "3") (pinfunction "3_3") (pintype "passive"))
    )
    (net (code "190") (name "Net-(IC36A-Y2)") (class "Default")
      (node (ref "IC36") (pin "6") (pinfunction "Y2_6") (pintype "output"))
      (node (ref "J2") (pin "5") (pinfunction "5_5") (pintype "passive"))
      (node (ref "J3") (pin "5") (pinfunction "5_5") (pintype "passive"))
    )
    (net (code "191") (name "Net-(IC36A-Y3)") (class "Default")
      (node (ref "IC36") (pin "7") (pinfunction "Y3_7") (pintype "output"))
      (node (ref "J2") (pin "7") (pinfunction "7_7") (pintype "passive"))
      (node (ref "J3") (pin "7") (pinfunction "7_7") (pintype "passive"))
    )
    (net (code "192") (name "Net-(IC36B-G)") (class "Default")
      (node (ref "IC36") (pin "15") (pinfunction "G_15") (pintype "input"))
      (node (ref "IC39") (pin "6") (pinfunction "O_6") (pintype "output"))
    )
    (net (code "193") (name "Net-(IC36B-Y0)") (class "Default")
      (node (ref "IC36") (pin "12") (pinfunction "Y0_12") (pintype "output"))
      (node (ref "J4") (pin "1") (pinfunction "1_1") (pintype "passive"))
      (node (ref "J5") (pin "1") (pinfunction "1_1") (pintype "passive"))
    )
    (net (code "194") (name "Net-(IC36B-Y1)") (class "Default")
      (node (ref "IC36") (pin "11") (pinfunction "Y1_11") (pintype "output"))
      (node (ref "J4") (pin "3") (pinfunction "3_3") (pintype "passive"))
      (node (ref "J5") (pin "3") (pinfunction "3_3") (pintype "passive"))
    )
    (net (code "195") (name "Net-(IC36B-Y2)") (class "Default")
      (node (ref "IC36") (pin "10") (pinfunction "Y2_10") (pintype "output"))
      (node (ref "J4") (pin "5") (pinfunction "5_5") (pintype "passive"))
      (node (ref "J5") (pin "5") (pinfunction "5_5") (pintype "passive"))
    )
    (net (code "196") (name "Net-(IC36B-Y3)") (class "Default")
      (node (ref "IC36") (pin "9") (pinfunction "Y3_9") (pintype "output"))
      (node (ref "J4") (pin "7") (pinfunction "7_7") (pintype "passive"))
      (node (ref "J5") (pin "7") (pinfunction "7_7") (pintype "passive"))
    )
    (net (code "197") (name "Net-(IC39C-O)") (class "Default")
      (node (ref "IC39") (pin "8") (pinfunction "O_8") (pintype "output"))
      (node (ref "IC5") (pin "19") (pinfunction "G_19") (pintype "input"))
      (node (ref "IC6") (pin "19") (pinfunction "G_19") (pintype "input"))
    )
    (net (code "198") (name "Net-(IC39D-O)") (class "Default")
      (node (ref "IC39") (pin "11") (pinfunction "O_11") (pintype "output"))
      (node (ref "IC7") (pin "19") (pinfunction "G_19") (pintype "input"))
    )
    (net (code "199") (name "Net-(PWR-PadA)") (class "Default")
      (node (ref "PWR") (pin "A") (pinfunction "A_A") (pintype "passive"))
      (node (ref "R2") (pin "1") (pinfunction "1_1") (pintype "passive"))
    )
    (net (code "200") (name "REG-LD-ID0") (class "Default")
      (node (ref "IC37") (pin "14") (pinfunction "A_14") (pintype "input"))
      (node (ref "IC38") (pin "2") (pinfunction "A_2") (pintype "input"))
      (node (ref "X1") (pin "B13") (pinfunction "B_B13") (pintype "passive"))
    )
    (net (code "201") (name "REG-LD-ID1") (class "Default")
      (node (ref "IC37") (pin "13") (pinfunction "B_13") (pintype "input"))
      (node (ref "IC38") (pin "3") (pinfunction "B_3") (pintype "input"))
      (node (ref "X1") (pin "B14") (pinfunction "B_B14") (pintype "passive"))
    )
    (net (code "202") (name "REG-LD-ID2") (class "Default")
      (node (ref "IC36") (pin "14") (pinfunction "A_14") (pintype "input"))
      (node (ref "X1") (pin "B15") (pinfunction "B_B15") (pintype "passive"))
    )
    (net (code "203") (name "REG-LD-ID3") (class "Default")
      (node (ref "IC36") (pin "13") (pinfunction "B_13") (pintype "input"))
      (node (ref "X1") (pin "B16") (pinfunction "B_B16") (pintype "passive"))
    )
    (net (code "204") (name "REG-RD-ID0") (class "Default")
      (node (ref "IC37") (pin "2") (pinfunction "A_2") (pintype "input"))
      (node (ref "IC38") (pin "14") (pinfunction "A_14") (pintype "input"))
      (node (ref "X1") (pin "B9") (pinfunction "B_B9") (pintype "passive"))
    )
    (net (code "205") (name "REG-RD-ID1") (class "Default")
      (node (ref "IC37") (pin "3") (pinfunction "B_3") (pintype "input"))
      (node (ref "IC38") (pin "13") (pinfunction "B_13") (pintype "input"))
      (node (ref "X1") (pin "B10") (pinfunction "B_B10") (pintype "passive"))
    )
    (net (code "206") (name "REG-RD-ID2") (class "Default")
      (node (ref "IC36") (pin "2") (pinfunction "A_2") (pintype "input"))
      (node (ref "X1") (pin "B11") (pinfunction "B_B11") (pintype "passive"))
    )
    (net (code "207") (name "REG-RD-ID3") (class "Default")
      (node (ref "IC36") (pin "3") (pinfunction "B_3") (pintype "input"))
      (node (ref "X1") (pin "B12") (pinfunction "B_B12") (pintype "passive"))
    )
    (net (code "208") (name "UNUSED0") (class "Default")
      (node (ref "X1") (pin "C12") (pinfunction "B_C12") (pintype "passive"))
    )
    (net (code "209") (name "VCC") (class "Default")
      (node (ref "C1") (pin "1") (pinfunction "1_1") (pintype "passive"))
      (node (ref "C10") (pin "1") (pinfunction "1_1") (pintype "passive"))
      (node (ref "C11") (pin "1") (pinfunction "1_1") (pintype "passive"))
      (node (ref "C12") (pin "1") (pinfunction "1_1") (pintype "passive"))
      (node (ref "C13") (pin "1") (pinfunction "1_1") (pintype "passive"))
      (node (ref "C14") (pin "1") (pinfunction "1_1") (pintype "passive"))
      (node (ref "C15") (pin "1") (pinfunction "1_1") (pintype "passive"))
      (node (ref "C16") (pin "1") (pinfunction "1_1") (pintype "passive"))
      (node (ref "C17") (pin "1") (pinfunction "1_1") (pintype "passive"))
      (node (ref "C18") (pin "1") (pinfunction "1_1") (pintype "passive"))
      (node (ref "C19") (pin "1") (pinfunction "1_1") (pintype "passive"))
      (node (ref "C2") (pin "1") (pinfunction "1_1") (pintype "passive"))
      (node (ref "C20") (pin "1") (pinfunction "1_1") (pintype "passive"))
      (node (ref "C21") (pin "1") (pinfunction "1_1") (pintype "passive"))
      (node (ref "C22") (pin "1") (pinfunction "1_1") (pintype "passive"))
      (node (ref "C23") (pin "1") (pinfunction "1_1") (pintype "passive"))
      (node (ref "C24") (pin "1") (pinfunction "1_1") (pintype "passive"))
      (node (ref "C25") (pin "1") (pinfunction "1_1") (pintype "passive"))
      (node (ref "C26") (pin "1") (pinfunction "1_1") (pintype "passive"))
      (node (ref "C27") (pin "1") (pinfunction "1_1") (pintype "passive"))
      (node (ref "C28") (pin "1") (pinfunction "1_1") (pintype "passive"))
      (node (ref "C29") (pin "1") (pinfunction "1_1") (pintype "passive"))
      (node (ref "C3") (pin "1") (pinfunction "1_1") (pintype "passive"))
      (node (ref "C30") (pin "1") (pinfunction "1_1") (pintype "passive"))
      (node (ref "C31") (pin "1") (pinfunction "1_1") (pintype "passive"))
      (node (ref "C32") (pin "1") (pinfunction "1_1") (pintype "passive"))
      (node (ref "C33") (pin "1") (pinfunction "1_1") (pintype "passive"))
      (node (ref "C34") (pin "1") (pinfunction "1_1") (pintype "passive"))
      (node (ref "C35") (pin "1") (pinfunction "1_1") (pintype "passive"))
      (node (ref "C36") (pin "1") (pinfunction "1_1") (pintype "passive"))
      (node (ref "C37") (pin "1") (pinfunction "1_1") (pintype "passive"))
      (node (ref "C38") (pin "1") (pinfunction "1_1") (pintype "passive"))
      (node (ref "C4") (pin "1") (pinfunction "1_1") (pintype "passive"))
      (node (ref "C5") (pin "1") (pinfunction "1_1") (pintype "passive"))
      (node (ref "C6") (pin "1") (pinfunction "1_1") (pintype "passive"))
      (node (ref "C7") (pin "1") (pinfunction "1_1") (pintype "passive"))
      (node (ref "C8") (pin "1") (pinfunction "1_1") (pintype "passive"))
      (node (ref "C9") (pin "1") (pinfunction "1_1") (pintype "passive"))
      (node (ref "IC2") (pin "12") (pinfunction "I0_12") (pintype "input"))
      (node (ref "IC2") (pin "9") (pinfunction "I0_9") (pintype "input"))
      (node (ref "JP1") (pin "1") (pinfunction "1_1") (pintype "passive"))
      (node (ref "JP1") (pin "2") (pinfunction "2_2") (pintype "passive"))
      (node (ref "R1") (pin "2") (pinfunction "2_2") (pintype "passive"))
      (node (ref "R2") (pin "2") (pinfunction "2_2") (pintype "passive"))
      (node (ref "R3") (pin "2") (pinfunction "2_2") (pintype "passive"))
      (node (ref "R4") (pin "2") (pinfunction "2_2") (pintype "passive"))
      (node (ref "R5") (pin "2") (pinfunction "2_2") (pintype "passive"))
      (node (ref "R6") (pin "2") (pinfunction "2_2") (pintype "passive"))
      (node (ref "RN1") (pin "1") (pinfunction "1_1") (pintype "passive"))
      (node (ref "RN2") (pin "1") (pinfunction "1_1") (pintype "passive"))
      (node (ref "X1") (pin "A2") (pinfunction "B_A2") (pintype "passive"))
      (node (ref "X1") (pin "A31") (pinfunction "B_A31") (pintype "passive"))
      (node (ref "X1") (pin "B2") (pinfunction "B_B2") (pintype "passive"))
      (node (ref "X1") (pin "B31") (pinfunction "B_B31") (pintype "passive"))
      (node (ref "X1") (pin "C2") (pinfunction "B_C2") (pintype "passive"))
      (node (ref "X1") (pin "C31") (pinfunction "B_C31") (pintype "passive"))
    )
    (net (code "210") (name "unconnected-(IC1B-O-Pad4)") (class "Default")
      (node (ref "IC1") (pin "4") (pinfunction "O_4") (pintype "open_collector"))
    )
    (net (code "211") (name "unconnected-(IC2A-O-Pad3)") (class "Default")
      (node (ref "IC2") (pin "3") (pinfunction "O_3") (pintype "output"))
    )
    (net (code "212") (name "unconnected-(IC2B-O-Pad6)") (class "Default")
      (node (ref "IC2") (pin "6") (pinfunction "O_6") (pintype "output"))
    )
    (net (code "213") (name "unconnected-(IC40E-O-Pad10)") (class "Default")
      (node (ref "IC40") (pin "10") (pinfunction "O_10") (pintype "open_collector"))
    )
    (net (code "214") (name "unconnected-(IC40F-O-Pad12)") (class "Default")
      (node (ref "IC40") (pin "12") (pinfunction "O_12") (pintype "open_collector"))
    )
    (net (code "215") (name "unconnected-(JP1-Pad35)") (class "Default")
      (node (ref "JP1") (pin "35") (pinfunction "35_35") (pintype "passive"))
    )
    (net (code "216") (name "unconnected-(JP1-Pad36)") (class "Default")
      (node (ref "JP1") (pin "36") (pinfunction "36_36") (pintype "passive"))
    )
    (net (code "217") (name "unconnected-(JP1-Pad37)") (class "Default")
      (node (ref "JP1") (pin "37") (pinfunction "37_37") (pintype "passive"))
    )
    (net (code "218") (name "unconnected-(JP1-Pad38)") (class "Default")
      (node (ref "JP1") (pin "38") (pinfunction "38_38") (pintype "passive"))
    )
  )
)
